# Tyr.net
KiCad netlist of a schematic drawn in EAGLE
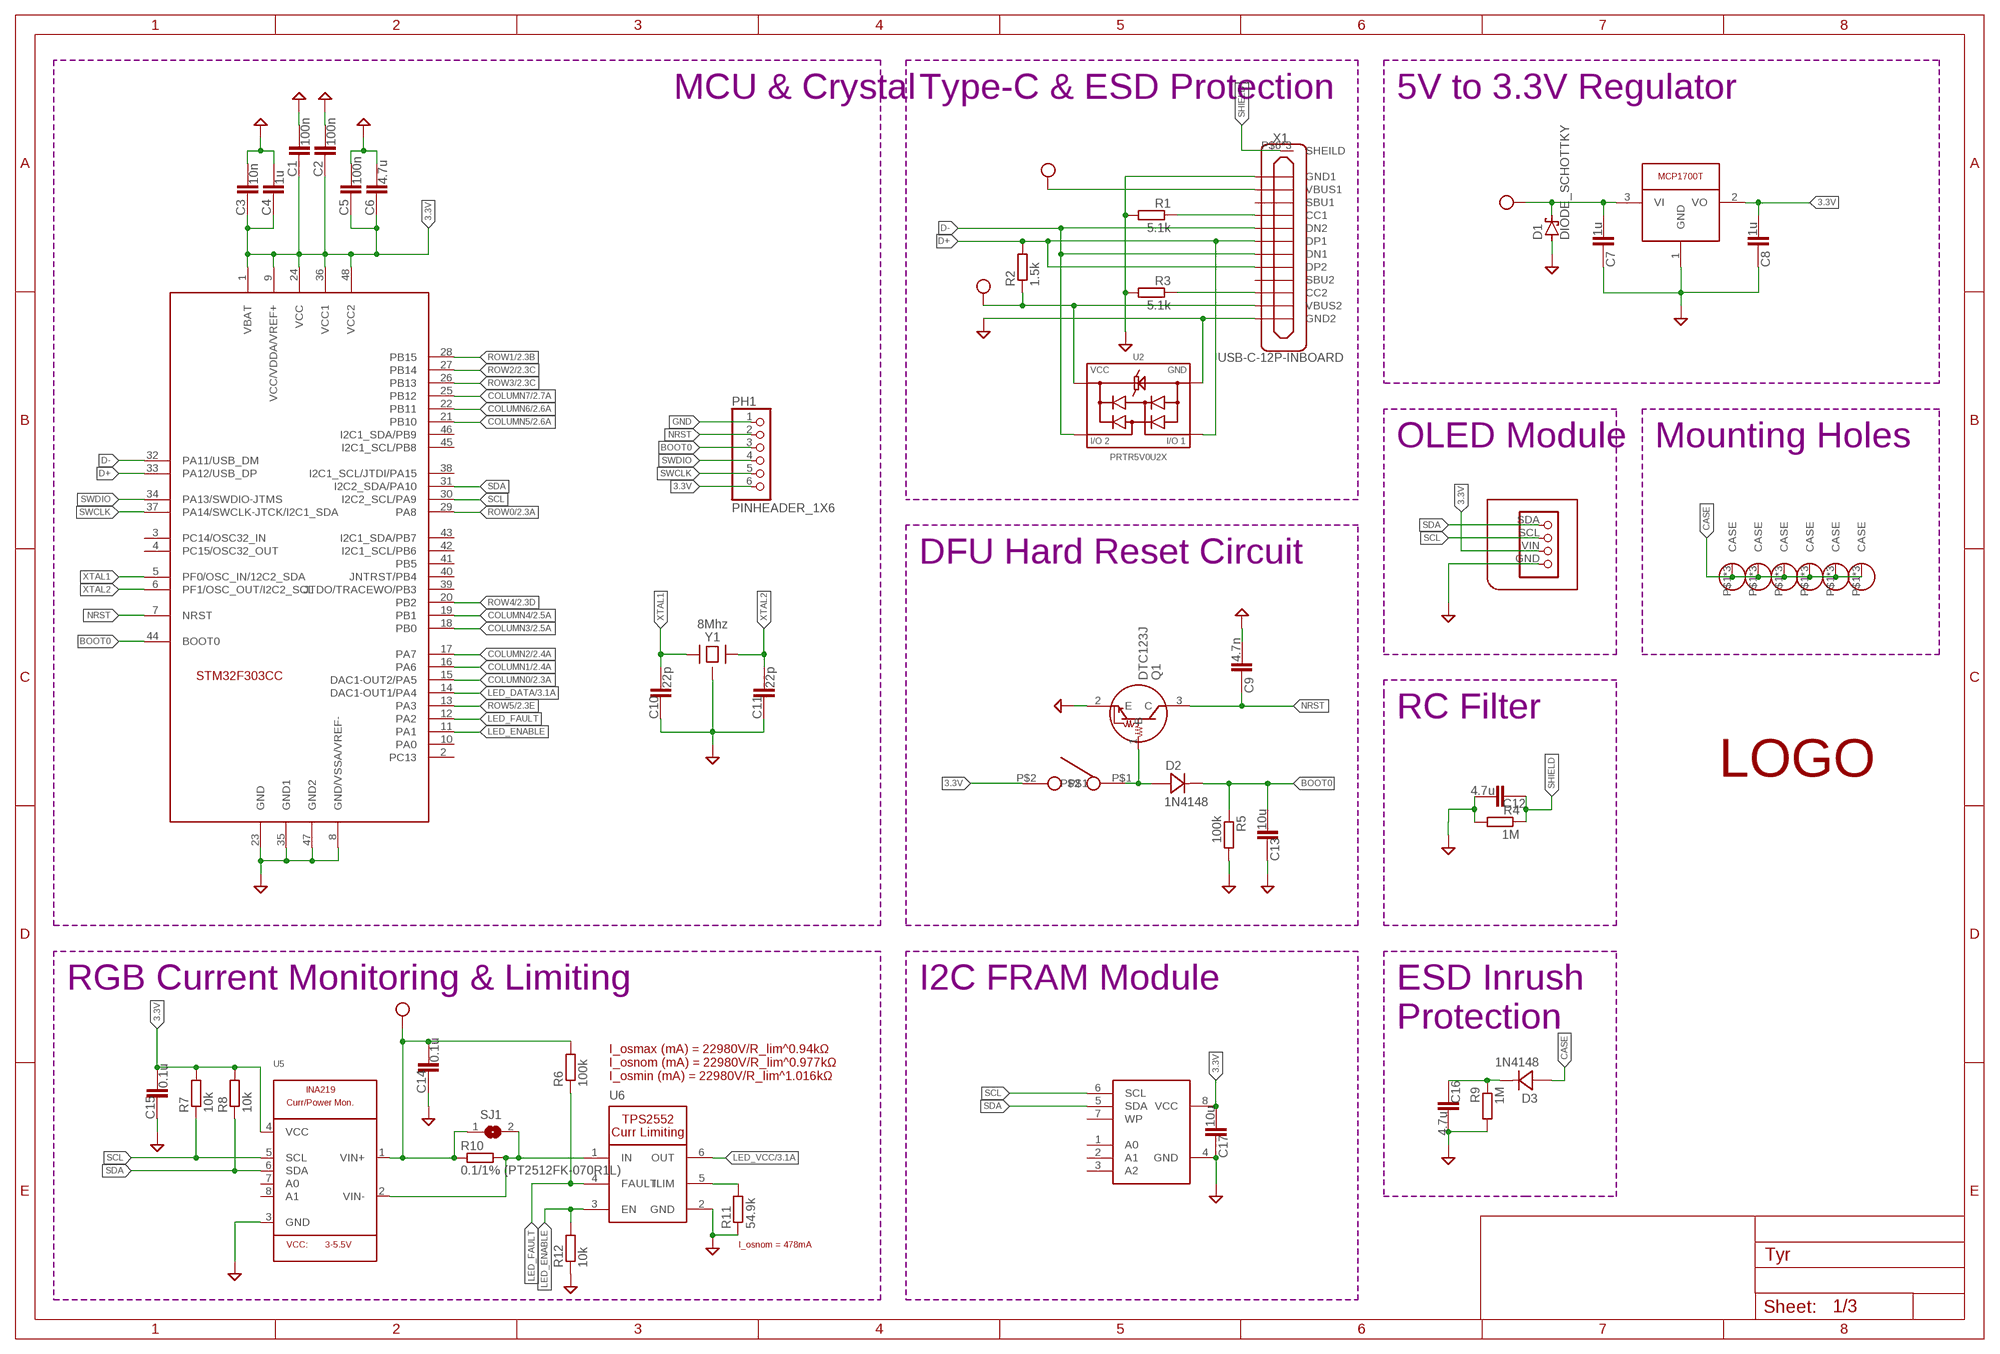
[diagram p0: schematic, sheet 1]
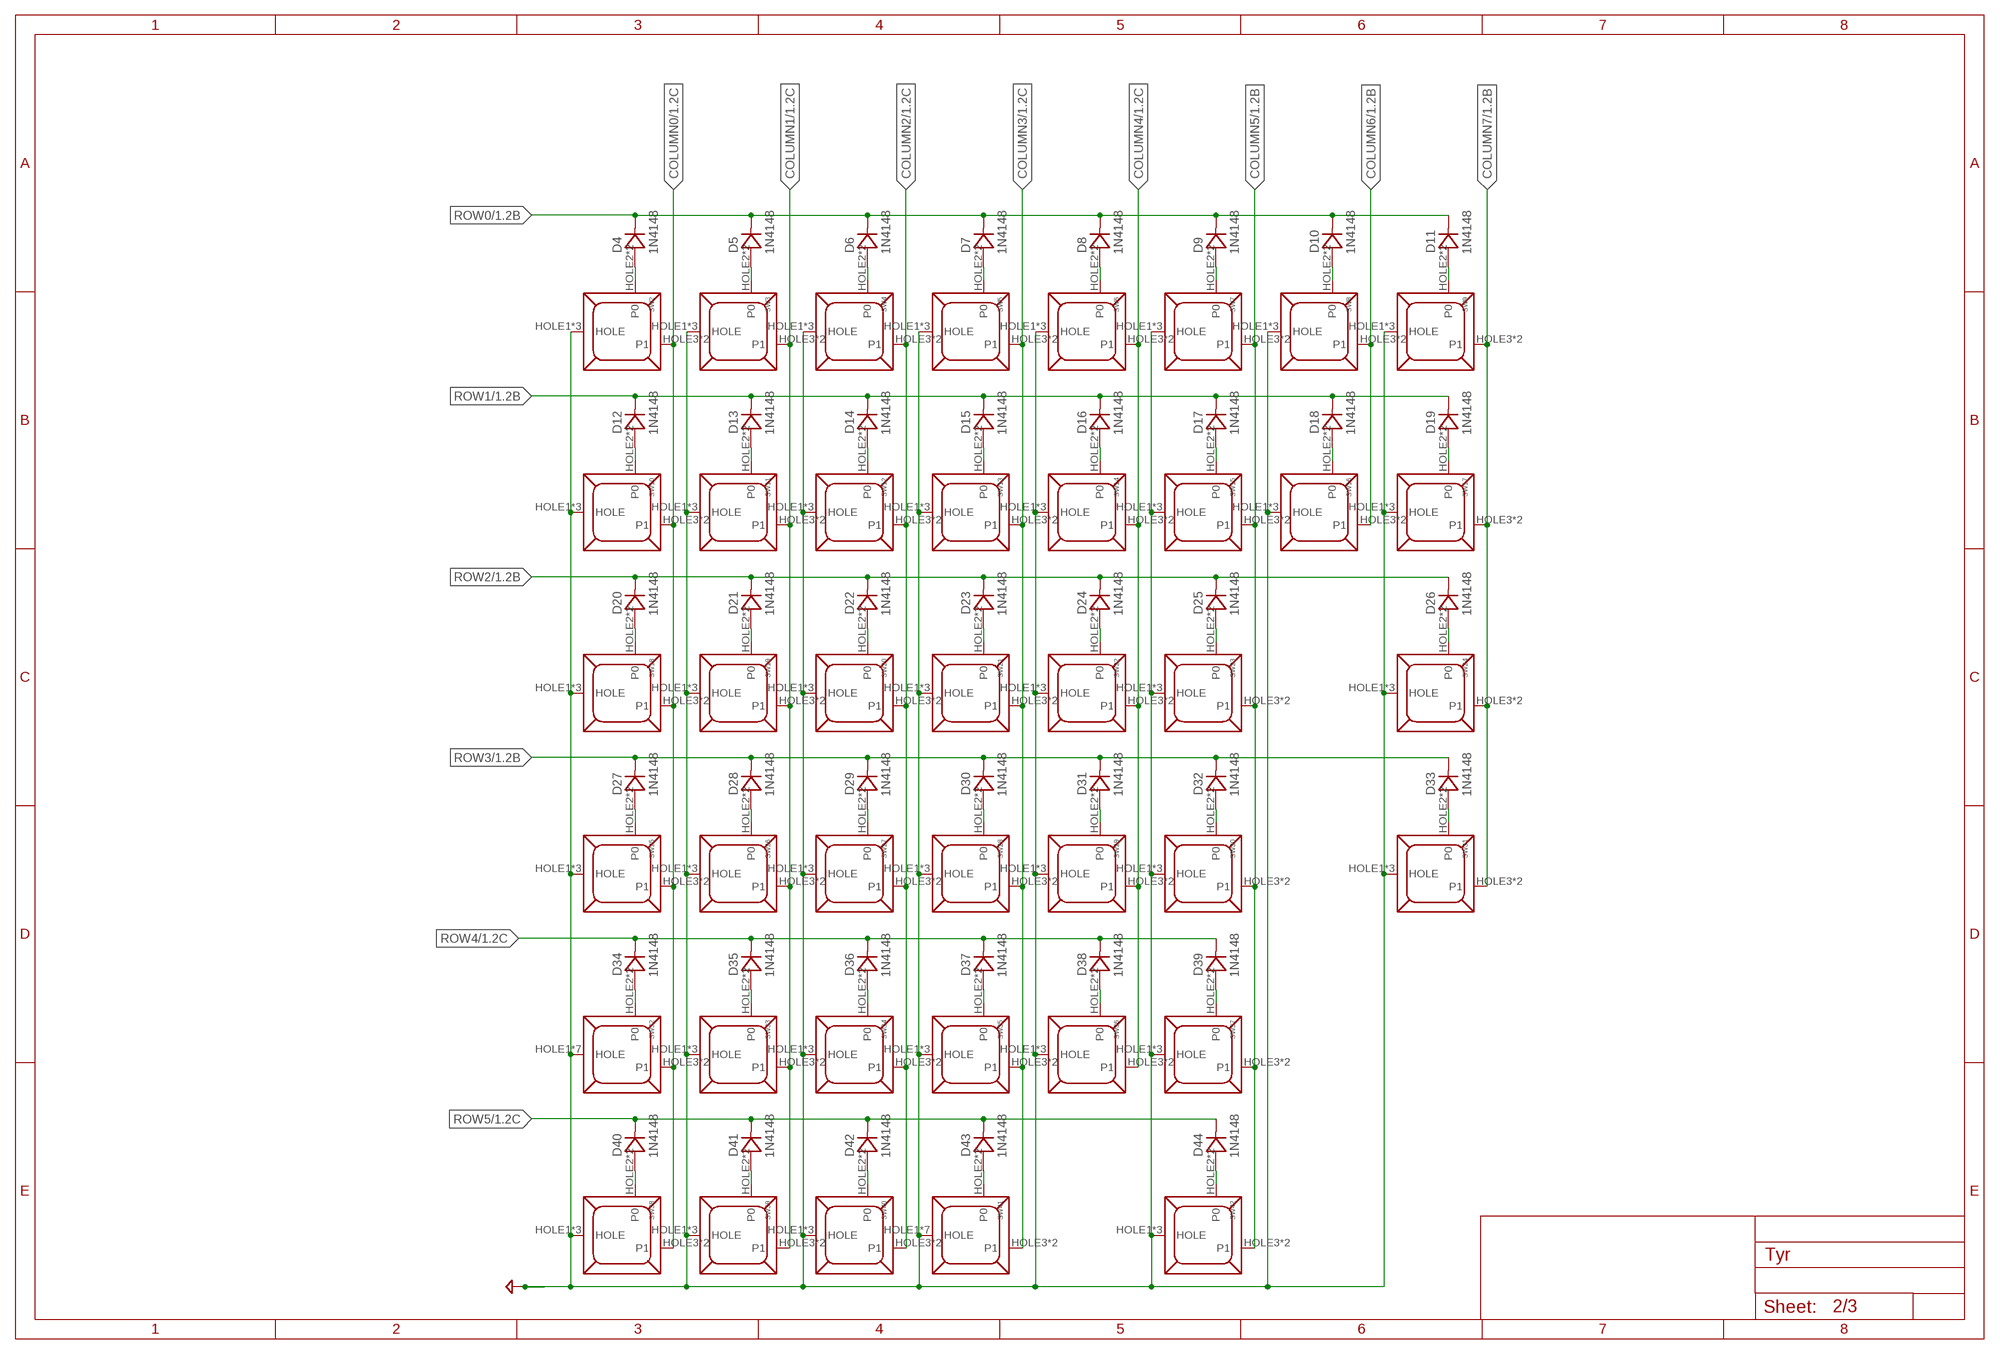
[diagram p1: schematic, sheet 2]
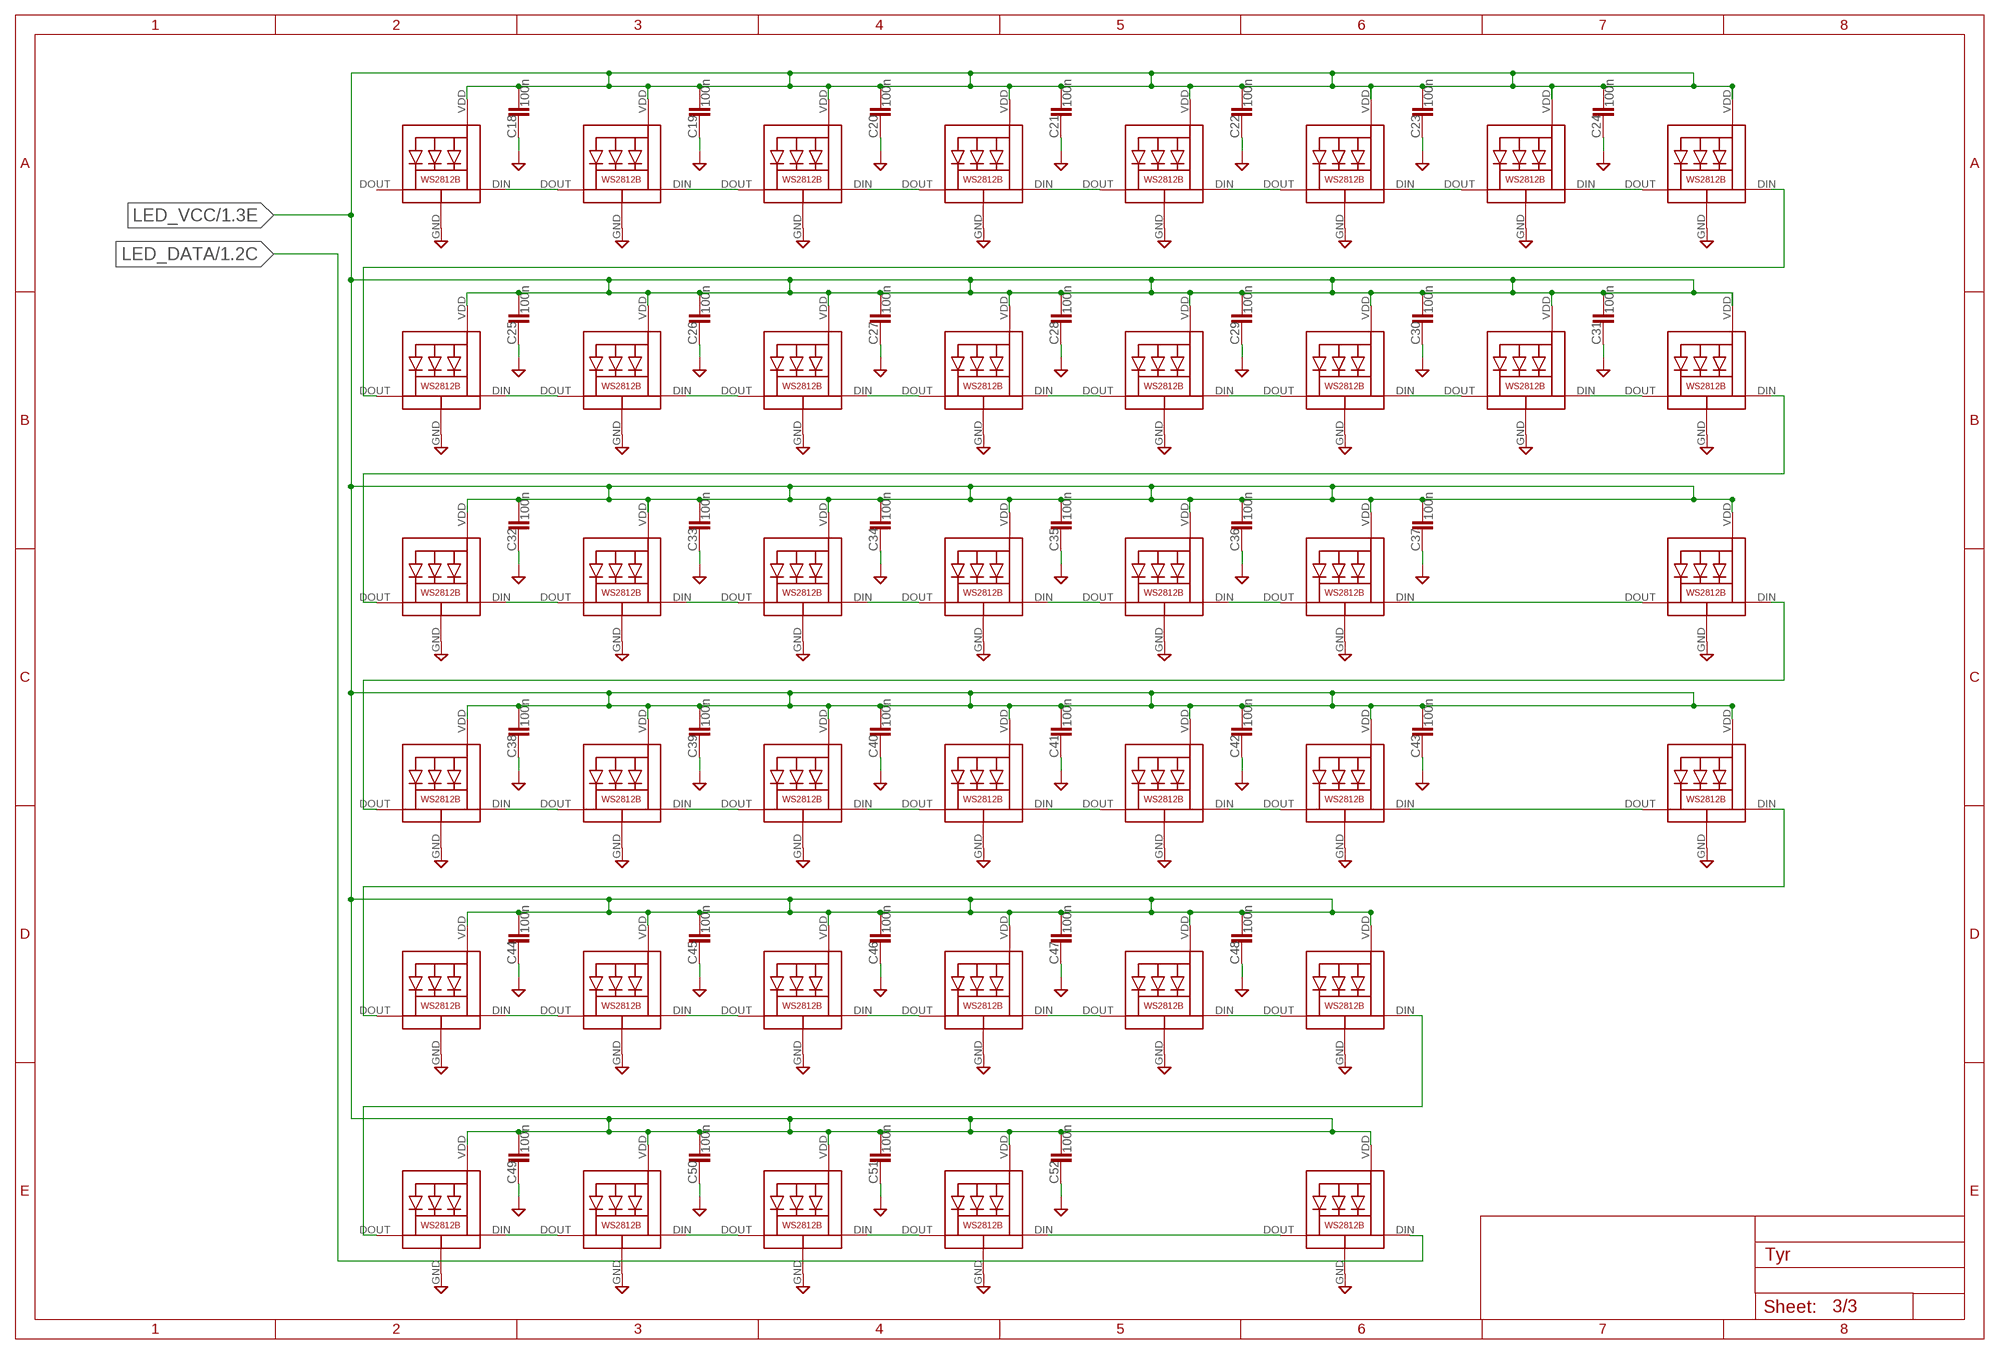
[diagram p2: schematic, sheet 3]

(export (version "E")
  (design (tool "Eeschema 10.0.6"))
  (components
    (comp (ref "D4")
      (value "1N4148")
      (footprint "eagle-import:SOD-123")
      (libsource (lib "eagle-import") (part "DIODE-SOD-123"))
    )
    (comp (ref "D5")
      (value "1N4148")
      (footprint "eagle-import:SOD-123")
      (libsource (lib "eagle-import") (part "DIODE-SOD-123"))
    )
    (comp (ref "D6")
      (value "1N4148")
      (footprint "eagle-import:SOD-123")
      (libsource (lib "eagle-import") (part "DIODE-SOD-123"))
    )
    (comp (ref "D7")
      (value "1N4148")
      (footprint "eagle-import:SOD-123")
      (libsource (lib "eagle-import") (part "DIODE-SOD-123"))
    )
    (comp (ref "D8")
      (value "1N4148")
      (footprint "eagle-import:SOD-123")
      (libsource (lib "eagle-import") (part "DIODE-SOD-123"))
    )
    (comp (ref "D9")
      (value "1N4148")
      (footprint "eagle-import:SOD-123")
      (libsource (lib "eagle-import") (part "DIODE-SOD-123"))
    )
    (comp (ref "D10")
      (value "1N4148")
      (footprint "eagle-import:SOD-123")
      (libsource (lib "eagle-import") (part "DIODE-SOD-123"))
    )
    (comp (ref "D11")
      (value "1N4148")
      (footprint "eagle-import:SOD-123")
      (libsource (lib "eagle-import") (part "DIODE-SOD-123"))
    )
    (comp (ref "D12")
      (value "1N4148")
      (footprint "eagle-import:SOD-123")
      (libsource (lib "eagle-import") (part "DIODE-SOD-123"))
    )
    (comp (ref "D13")
      (value "1N4148")
      (footprint "eagle-import:SOD-123")
      (libsource (lib "eagle-import") (part "DIODE-SOD-123"))
    )
    (comp (ref "D14")
      (value "1N4148")
      (footprint "eagle-import:SOD-123")
      (libsource (lib "eagle-import") (part "DIODE-SOD-123"))
    )
    (comp (ref "D15")
      (value "1N4148")
      (footprint "eagle-import:SOD-123")
      (libsource (lib "eagle-import") (part "DIODE-SOD-123"))
    )
    (comp (ref "D16")
      (value "1N4148")
      (footprint "eagle-import:SOD-123")
      (libsource (lib "eagle-import") (part "DIODE-SOD-123"))
    )
    (comp (ref "D17")
      (value "1N4148")
      (footprint "eagle-import:SOD-123")
      (libsource (lib "eagle-import") (part "DIODE-SOD-123"))
    )
    (comp (ref "D18")
      (value "1N4148")
      (footprint "eagle-import:SOD-123")
      (libsource (lib "eagle-import") (part "DIODE-SOD-123"))
    )
    (comp (ref "D19")
      (value "1N4148")
      (footprint "eagle-import:SOD-123")
      (libsource (lib "eagle-import") (part "DIODE-SOD-123"))
    )
    (comp (ref "D20")
      (value "1N4148")
      (footprint "eagle-import:SOD-123")
      (libsource (lib "eagle-import") (part "DIODE-SOD-123"))
    )
    (comp (ref "D21")
      (value "1N4148")
      (footprint "eagle-import:SOD-123")
      (libsource (lib "eagle-import") (part "DIODE-SOD-123"))
    )
    (comp (ref "D22")
      (value "1N4148")
      (footprint "eagle-import:SOD-123")
      (libsource (lib "eagle-import") (part "DIODE-SOD-123"))
    )
    (comp (ref "D23")
      (value "1N4148")
      (footprint "eagle-import:SOD-123")
      (libsource (lib "eagle-import") (part "DIODE-SOD-123"))
    )
    (comp (ref "D24")
      (value "1N4148")
      (footprint "eagle-import:SOD-123")
      (libsource (lib "eagle-import") (part "DIODE-SOD-123"))
    )
    (comp (ref "D25")
      (value "1N4148")
      (footprint "eagle-import:SOD-123")
      (libsource (lib "eagle-import") (part "DIODE-SOD-123"))
    )
    (comp (ref "D26")
      (value "1N4148")
      (footprint "eagle-import:SOD-123")
      (libsource (lib "eagle-import") (part "DIODE-SOD-123"))
    )
    (comp (ref "D27")
      (value "1N4148")
      (footprint "eagle-import:SOD-123")
      (libsource (lib "eagle-import") (part "DIODE-SOD-123"))
    )
    (comp (ref "D28")
      (value "1N4148")
      (footprint "eagle-import:SOD-123")
      (libsource (lib "eagle-import") (part "DIODE-SOD-123"))
    )
    (comp (ref "D29")
      (value "1N4148")
      (footprint "eagle-import:SOD-123")
      (libsource (lib "eagle-import") (part "DIODE-SOD-123"))
    )
    (comp (ref "D30")
      (value "1N4148")
      (footprint "eagle-import:SOD-123")
      (libsource (lib "eagle-import") (part "DIODE-SOD-123"))
    )
    (comp (ref "D31")
      (value "1N4148")
      (footprint "eagle-import:SOD-123")
      (libsource (lib "eagle-import") (part "DIODE-SOD-123"))
    )
    (comp (ref "D32")
      (value "1N4148")
      (footprint "eagle-import:SOD-123")
      (libsource (lib "eagle-import") (part "DIODE-SOD-123"))
    )
    (comp (ref "D33")
      (value "1N4148")
      (footprint "eagle-import:SOD-123")
      (libsource (lib "eagle-import") (part "DIODE-SOD-123"))
    )
    (comp (ref "D34")
      (value "1N4148")
      (footprint "eagle-import:SOD-123")
      (libsource (lib "eagle-import") (part "DIODE-SOD-123"))
    )
    (comp (ref "D35")
      (value "1N4148")
      (footprint "eagle-import:SOD-123")
      (libsource (lib "eagle-import") (part "DIODE-SOD-123"))
    )
    (comp (ref "D36")
      (value "1N4148")
      (footprint "eagle-import:SOD-123")
      (libsource (lib "eagle-import") (part "DIODE-SOD-123"))
    )
    (comp (ref "D37")
      (value "1N4148")
      (footprint "eagle-import:SOD-123")
      (libsource (lib "eagle-import") (part "DIODE-SOD-123"))
    )
    (comp (ref "D38")
      (value "1N4148")
      (footprint "eagle-import:SOD-123")
      (libsource (lib "eagle-import") (part "DIODE-SOD-123"))
    )
    (comp (ref "D39")
      (value "1N4148")
      (footprint "eagle-import:SOD-123")
      (libsource (lib "eagle-import") (part "DIODE-SOD-123"))
    )
    (comp (ref "D40")
      (value "1N4148")
      (footprint "eagle-import:SOD-123")
      (libsource (lib "eagle-import") (part "DIODE-SOD-123"))
    )
    (comp (ref "D41")
      (value "1N4148")
      (footprint "eagle-import:SOD-123")
      (libsource (lib "eagle-import") (part "DIODE-SOD-123"))
    )
    (comp (ref "D42")
      (value "1N4148")
      (footprint "eagle-import:SOD-123")
      (libsource (lib "eagle-import") (part "DIODE-SOD-123"))
    )
    (comp (ref "D43")
      (value "1N4148")
      (footprint "eagle-import:SOD-123")
      (libsource (lib "eagle-import") (part "DIODE-SOD-123"))
    )
    (comp (ref "D44")
      (value "1N4148")
      (footprint "eagle-import:SOD-123")
      (libsource (lib "eagle-import") (part "DIODE-SOD-123"))
    )
    (comp (ref "SW2")
      (value "MX")
      (footprint "eagle-import:MX-1U-HOTSWAP")
      (libsource (lib "eagle-import") (part "KEYSWITCH-MX_PLATED-1U-HOTSWAP"))
    )
    (comp (ref "SW3")
      (value "MX")
      (footprint "eagle-import:MX-1U-HOTSWAP")
      (libsource (lib "eagle-import") (part "KEYSWITCH-MX_PLATED-1U-HOTSWAP"))
    )
    (comp (ref "SW4")
      (value "MX")
      (footprint "eagle-import:MX-1U-HOTSWAP")
      (libsource (lib "eagle-import") (part "KEYSWITCH-MX_PLATED-1U-HOTSWAP"))
    )
    (comp (ref "SW5")
      (value "MX")
      (footprint "eagle-import:MX-1U-HOTSWAP")
      (libsource (lib "eagle-import") (part "KEYSWITCH-MX_PLATED-1U-HOTSWAP"))
    )
    (comp (ref "SW6")
      (value "MX")
      (footprint "eagle-import:MX-1U-HOTSWAP")
      (libsource (lib "eagle-import") (part "KEYSWITCH-MX_PLATED-1U-HOTSWAP"))
    )
    (comp (ref "SW7")
      (value "MX")
      (footprint "eagle-import:MX-1U-HOTSWAP")
      (libsource (lib "eagle-import") (part "KEYSWITCH-MX_PLATED-1U-HOTSWAP"))
    )
    (comp (ref "SW8")
      (value "MX")
      (footprint "eagle-import:MX-1U-HOTSWAP")
      (libsource (lib "eagle-import") (part "KEYSWITCH-MX_PLATED-1U-HOTSWAP"))
    )
    (comp (ref "SW9")
      (value "MX")
      (footprint "eagle-import:MX-1U-HOTSWAP")
      (libsource (lib "eagle-import") (part "KEYSWITCH-MX_PLATED-1U-HOTSWAP"))
    )
    (comp (ref "SW10")
      (value "MX")
      (footprint "eagle-import:MX-1U-HOTSWAP")
      (libsource (lib "eagle-import") (part "KEYSWITCH-MX_PLATED-1U-HOTSWAP"))
    )
    (comp (ref "SW11")
      (value "MX")
      (footprint "eagle-import:MX-1U-HOTSWAP")
      (libsource (lib "eagle-import") (part "KEYSWITCH-MX_PLATED-1U-HOTSWAP"))
    )
    (comp (ref "SW12")
      (value "MX")
      (footprint "eagle-import:MX-1U-HOTSWAP")
      (libsource (lib "eagle-import") (part "KEYSWITCH-MX_PLATED-1U-HOTSWAP"))
    )
    (comp (ref "SW13")
      (value "MX")
      (footprint "eagle-import:MX-1U-HOTSWAP")
      (libsource (lib "eagle-import") (part "KEYSWITCH-MX_PLATED-1U-HOTSWAP"))
    )
    (comp (ref "SW14")
      (value "MX")
      (footprint "eagle-import:MX-1U-HOTSWAP")
      (libsource (lib "eagle-import") (part "KEYSWITCH-MX_PLATED-1U-HOTSWAP"))
    )
    (comp (ref "SW15")
      (value "MX")
      (footprint "eagle-import:MX-1U-HOTSWAP")
      (libsource (lib "eagle-import") (part "KEYSWITCH-MX_PLATED-1U-HOTSWAP"))
    )
    (comp (ref "SW16")
      (value "MX")
      (footprint "eagle-import:MX-1U-HOTSWAP")
      (libsource (lib "eagle-import") (part "KEYSWITCH-MX_PLATED-1U-HOTSWAP"))
    )
    (comp (ref "SW17")
      (value "MX")
      (footprint "eagle-import:MX-1U-HOTSWAP")
      (libsource (lib "eagle-import") (part "KEYSWITCH-MX_PLATED-1U-HOTSWAP"))
    )
    (comp (ref "SW18")
      (value "MX")
      (footprint "eagle-import:MX-1U-HOTSWAP")
      (libsource (lib "eagle-import") (part "KEYSWITCH-MX_PLATED-1U-HOTSWAP"))
    )
    (comp (ref "SW19")
      (value "MX")
      (footprint "eagle-import:MX-1U-HOTSWAP")
      (libsource (lib "eagle-import") (part "KEYSWITCH-MX_PLATED-1U-HOTSWAP"))
    )
    (comp (ref "SW20")
      (value "MX")
      (footprint "eagle-import:MX-1U-HOTSWAP")
      (libsource (lib "eagle-import") (part "KEYSWITCH-MX_PLATED-1U-HOTSWAP"))
    )
    (comp (ref "SW21")
      (value "MX")
      (footprint "eagle-import:MX-1U-HOTSWAP")
      (libsource (lib "eagle-import") (part "KEYSWITCH-MX_PLATED-1U-HOTSWAP"))
    )
    (comp (ref "SW22")
      (value "MX")
      (footprint "eagle-import:MX-1U-HOTSWAP")
      (libsource (lib "eagle-import") (part "KEYSWITCH-MX_PLATED-1U-HOTSWAP"))
    )
    (comp (ref "SW23")
      (value "MX")
      (footprint "eagle-import:MX-1U-HOTSWAP")
      (libsource (lib "eagle-import") (part "KEYSWITCH-MX_PLATED-1U-HOTSWAP"))
    )
    (comp (ref "SW24")
      (value "MX")
      (footprint "eagle-import:MX-1U-HOTSWAP")
      (libsource (lib "eagle-import") (part "KEYSWITCH-MX_PLATED-1U-HOTSWAP"))
    )
    (comp (ref "SW25")
      (value "MX")
      (footprint "eagle-import:MX-1U-HOTSWAP-CAPSLOCK")
      (libsource (lib "eagle-import") (part "KEYSWITCH-MX_PLATED-1U-HOTSWAP_CAPSLOCK"))
    )
    (comp (ref "SW26")
      (value "MX")
      (footprint "eagle-import:MX-1U-HOTSWAP")
      (libsource (lib "eagle-import") (part "KEYSWITCH-MX_PLATED-1U-HOTSWAP"))
    )
    (comp (ref "SW27")
      (value "MX")
      (footprint "eagle-import:MX-1U-HOTSWAP")
      (libsource (lib "eagle-import") (part "KEYSWITCH-MX_PLATED-1U-HOTSWAP"))
    )
    (comp (ref "SW28")
      (value "MX")
      (footprint "eagle-import:MX-1U-HOTSWAP")
      (libsource (lib "eagle-import") (part "KEYSWITCH-MX_PLATED-1U-HOTSWAP"))
    )
    (comp (ref "SW29")
      (value "MX")
      (footprint "eagle-import:MX-1U-HOTSWAP")
      (libsource (lib "eagle-import") (part "KEYSWITCH-MX_PLATED-1U-HOTSWAP"))
    )
    (comp (ref "SW30")
      (value "MX")
      (footprint "eagle-import:MX-1U-HOTSWAP")
      (libsource (lib "eagle-import") (part "KEYSWITCH-MX_PLATED-1U-HOTSWAP"))
    )
    (comp (ref "SW31")
      (value "MX")
      (footprint "eagle-import:MX-1U-HOTSWAP")
      (libsource (lib "eagle-import") (part "KEYSWITCH-MX_PLATED-1U-HOTSWAP"))
    )
    (comp (ref "SW32")
      (value "MX")
      (footprint "eagle-import:MX-2U-HOTSWAP")
      (libsource (lib "eagle-import") (part "KEYSWITCH-MX_PLATED-2U-HOTSWAP"))
    )
    (comp (ref "SW33")
      (value "MX")
      (footprint "eagle-import:MX-1U-HOTSWAP")
      (libsource (lib "eagle-import") (part "KEYSWITCH-MX_PLATED-1U-HOTSWAP"))
    )
    (comp (ref "SW34")
      (value "MX")
      (footprint "eagle-import:MX-1U-HOTSWAP")
      (libsource (lib "eagle-import") (part "KEYSWITCH-MX_PLATED-1U-HOTSWAP"))
    )
    (comp (ref "SW35")
      (value "MX")
      (footprint "eagle-import:MX-1U-HOTSWAP")
      (libsource (lib "eagle-import") (part "KEYSWITCH-MX_PLATED-1U-HOTSWAP"))
    )
    (comp (ref "SW36")
      (value "MX")
      (footprint "eagle-import:MX-1U-HOTSWAP")
      (libsource (lib "eagle-import") (part "KEYSWITCH-MX_PLATED-1U-HOTSWAP"))
    )
    (comp (ref "SW37")
      (value "MX")
      (footprint "eagle-import:MX-1U-HOTSWAP")
      (libsource (lib "eagle-import") (part "KEYSWITCH-MX_PLATED-1U-HOTSWAP"))
    )
    (comp (ref "SW38")
      (value "MX")
      (footprint "eagle-import:MX-1U-HOTSWAP")
      (libsource (lib "eagle-import") (part "KEYSWITCH-MX_PLATED-1U-HOTSWAP"))
    )
    (comp (ref "SW39")
      (value "MX")
      (footprint "eagle-import:MX-1U-HOTSWAP")
      (libsource (lib "eagle-import") (part "KEYSWITCH-MX_PLATED-1U-HOTSWAP"))
    )
    (comp (ref "SW40")
      (value "MX")
      (footprint "eagle-import:MX-1U-HOTSWAP")
      (libsource (lib "eagle-import") (part "KEYSWITCH-MX_PLATED-1U-HOTSWAP"))
    )
    (comp (ref "SW41")
      (value "MX")
      (footprint "eagle-import:MX-2U-HOTSWAP")
      (libsource (lib "eagle-import") (part "KEYSWITCH-MX_PLATED-2U-HOTSWAP"))
    )
    (comp (ref "SW42")
      (value "MX")
      (footprint "eagle-import:MX-1U-HOTSWAP")
      (libsource (lib "eagle-import") (part "KEYSWITCH-MX_PLATED-1U-HOTSWAP"))
    )
    (comp (ref "C18")
      (value "100n")
      (footprint "eagle-import:C0603")
      (libsource (lib "eagle-import") (part "CAPACITOR-0603"))
    )
    (comp (ref "C19")
      (value "100n")
      (footprint "eagle-import:C0603")
      (libsource (lib "eagle-import") (part "CAPACITOR-0603"))
    )
    (comp (ref "C20")
      (value "100n")
      (footprint "eagle-import:C0603")
      (libsource (lib "eagle-import") (part "CAPACITOR-0603"))
    )
    (comp (ref "C21")
      (value "100n")
      (footprint "eagle-import:C0603")
      (libsource (lib "eagle-import") (part "CAPACITOR-0603"))
    )
    (comp (ref "C22")
      (value "100n")
      (footprint "eagle-import:C0603")
      (libsource (lib "eagle-import") (part "CAPACITOR-0603"))
    )
    (comp (ref "C23")
      (value "100n")
      (footprint "eagle-import:C0603")
      (libsource (lib "eagle-import") (part "CAPACITOR-0603"))
    )
    (comp (ref "C24")
      (value "100n")
      (footprint "eagle-import:C0603")
      (libsource (lib "eagle-import") (part "CAPACITOR-0603"))
    )
    (comp (ref "C25")
      (value "100n")
      (footprint "eagle-import:C0603")
      (libsource (lib "eagle-import") (part "CAPACITOR-0603"))
    )
    (comp (ref "C26")
      (value "100n")
      (footprint "eagle-import:C0603")
      (libsource (lib "eagle-import") (part "CAPACITOR-0603"))
    )
    (comp (ref "C27")
      (value "100n")
      (footprint "eagle-import:C0603")
      (libsource (lib "eagle-import") (part "CAPACITOR-0603"))
    )
    (comp (ref "C28")
      (value "100n")
      (footprint "eagle-import:C0603")
      (libsource (lib "eagle-import") (part "CAPACITOR-0603"))
    )
    (comp (ref "C29")
      (value "100n")
      (footprint "eagle-import:C0603")
      (libsource (lib "eagle-import") (part "CAPACITOR-0603"))
    )
    (comp (ref "C30")
      (value "100n")
      (footprint "eagle-import:C0603")
      (libsource (lib "eagle-import") (part "CAPACITOR-0603"))
    )
    (comp (ref "C31")
      (value "100n")
      (footprint "eagle-import:C0603")
      (libsource (lib "eagle-import") (part "CAPACITOR-0603"))
    )
    (comp (ref "C32")
      (value "100n")
      (footprint "eagle-import:C0603")
      (libsource (lib "eagle-import") (part "CAPACITOR-0603"))
    )
    (comp (ref "C33")
      (value "100n")
      (footprint "eagle-import:C0603")
      (libsource (lib "eagle-import") (part "CAPACITOR-0603"))
    )
    (comp (ref "C34")
      (value "100n")
      (footprint "eagle-import:C0603")
      (libsource (lib "eagle-import") (part "CAPACITOR-0603"))
    )
    (comp (ref "C35")
      (value "100n")
      (footprint "eagle-import:C0603")
      (libsource (lib "eagle-import") (part "CAPACITOR-0603"))
    )
    (comp (ref "C36")
      (value "100n")
      (footprint "eagle-import:C0603")
      (libsource (lib "eagle-import") (part "CAPACITOR-0603"))
    )
    (comp (ref "C37")
      (value "100n")
      (footprint "eagle-import:C0603")
      (libsource (lib "eagle-import") (part "CAPACITOR-0603"))
    )
    (comp (ref "C38")
      (value "100n")
      (footprint "eagle-import:C0603")
      (libsource (lib "eagle-import") (part "CAPACITOR-0603"))
    )
    (comp (ref "C39")
      (value "100n")
      (footprint "eagle-import:C0603")
      (libsource (lib "eagle-import") (part "CAPACITOR-0603"))
    )
    (comp (ref "C40")
      (value "100n")
      (footprint "eagle-import:C0603")
      (libsource (lib "eagle-import") (part "CAPACITOR-0603"))
    )
    (comp (ref "C41")
      (value "100n")
      (footprint "eagle-import:C0603")
      (libsource (lib "eagle-import") (part "CAPACITOR-0603"))
    )
    (comp (ref "C42")
      (value "100n")
      (footprint "eagle-import:C0603")
      (libsource (lib "eagle-import") (part "CAPACITOR-0603"))
    )
    (comp (ref "C43")
      (value "100n")
      (footprint "eagle-import:C0603")
      (libsource (lib "eagle-import") (part "CAPACITOR-0603"))
    )
    (comp (ref "C44")
      (value "100n")
      (footprint "eagle-import:C0603")
      (libsource (lib "eagle-import") (part "CAPACITOR-0603"))
    )
    (comp (ref "C45")
      (value "100n")
      (footprint "eagle-import:C0603")
      (libsource (lib "eagle-import") (part "CAPACITOR-0603"))
    )
    (comp (ref "C46")
      (value "100n")
      (footprint "eagle-import:C0603")
      (libsource (lib "eagle-import") (part "CAPACITOR-0603"))
    )
    (comp (ref "C47")
      (value "100n")
      (footprint "eagle-import:C0603")
      (libsource (lib "eagle-import") (part "CAPACITOR-0603"))
    )
    (comp (ref "C48")
      (value "100n")
      (footprint "eagle-import:C0603")
      (libsource (lib "eagle-import") (part "CAPACITOR-0603"))
    )
    (comp (ref "C49")
      (value "100n")
      (footprint "eagle-import:C0603")
      (libsource (lib "eagle-import") (part "CAPACITOR-0603"))
    )
    (comp (ref "C50")
      (value "100n")
      (footprint "eagle-import:C0603")
      (libsource (lib "eagle-import") (part "CAPACITOR-0603"))
    )
    (comp (ref "C51")
      (value "100n")
      (footprint "eagle-import:C0603")
      (libsource (lib "eagle-import") (part "CAPACITOR-0603"))
    )
    (comp (ref "C52")
      (value "100n")
      (footprint "eagle-import:C0603")
      (libsource (lib "eagle-import") (part "CAPACITOR-0603"))
    )
    (comp (ref "LED1")
      (value "WS2812B_3528_REVERS-MOUNT")
      (footprint "eagle-import:WS2812B_3528_REVERS-MOUNT")
      (libsource (lib "eagle-import") (part "WS2812B_3528_REVERS-MOUNT"))
    )
    (comp (ref "LED2")
      (value "WS2812B_3528_REVERS-MOUNT")
      (footprint "eagle-import:WS2812B_3528_REVERS-MOUNT")
      (libsource (lib "eagle-import") (part "WS2812B_3528_REVERS-MOUNT"))
    )
    (comp (ref "LED3")
      (value "WS2812B_3528_REVERS-MOUNT")
      (footprint "eagle-import:WS2812B_3528_REVERS-MOUNT")
      (libsource (lib "eagle-import") (part "WS2812B_3528_REVERS-MOUNT"))
    )
    (comp (ref "LED4")
      (value "WS2812B_3528_REVERS-MOUNT")
      (footprint "eagle-import:WS2812B_3528_REVERS-MOUNT")
      (libsource (lib "eagle-import") (part "WS2812B_3528_REVERS-MOUNT"))
    )
    (comp (ref "LED5")
      (value "WS2812B_3528_REVERS-MOUNT")
      (footprint "eagle-import:WS2812B_3528_REVERS-MOUNT")
      (libsource (lib "eagle-import") (part "WS2812B_3528_REVERS-MOUNT"))
    )
    (comp (ref "LED6")
      (value "WS2812B_3528_REVERS-MOUNT")
      (footprint "eagle-import:WS2812B_3528_REVERS-MOUNT")
      (libsource (lib "eagle-import") (part "WS2812B_3528_REVERS-MOUNT"))
    )
    (comp (ref "LED7")
      (value "WS2812B_3528_REVERS-MOUNT")
      (footprint "eagle-import:WS2812B_3528_REVERS-MOUNT")
      (libsource (lib "eagle-import") (part "WS2812B_3528_REVERS-MOUNT"))
    )
    (comp (ref "LED8")
      (value "WS2812B_3528_REVERS-MOUNT")
      (footprint "eagle-import:WS2812B_3528_REVERS-MOUNT")
      (libsource (lib "eagle-import") (part "WS2812B_3528_REVERS-MOUNT"))
    )
    (comp (ref "LED9")
      (value "WS2812B_3528_REVERS-MOUNT")
      (footprint "eagle-import:WS2812B_3528_REVERS-MOUNT")
      (libsource (lib "eagle-import") (part "WS2812B_3528_REVERS-MOUNT"))
    )
    (comp (ref "LED10")
      (value "WS2812B_3528_REVERS-MOUNT")
      (footprint "eagle-import:WS2812B_3528_REVERS-MOUNT")
      (libsource (lib "eagle-import") (part "WS2812B_3528_REVERS-MOUNT"))
    )
    (comp (ref "LED11")
      (value "WS2812B_3528_REVERS-MOUNT")
      (footprint "eagle-import:WS2812B_3528_REVERS-MOUNT")
      (libsource (lib "eagle-import") (part "WS2812B_3528_REVERS-MOUNT"))
    )
    (comp (ref "LED12")
      (value "WS2812B_3528_REVERS-MOUNT")
      (footprint "eagle-import:WS2812B_3528_REVERS-MOUNT")
      (libsource (lib "eagle-import") (part "WS2812B_3528_REVERS-MOUNT"))
    )
    (comp (ref "LED13")
      (value "WS2812B_3528_REVERS-MOUNT")
      (footprint "eagle-import:WS2812B_3528_REVERS-MOUNT")
      (libsource (lib "eagle-import") (part "WS2812B_3528_REVERS-MOUNT"))
    )
    (comp (ref "LED14")
      (value "WS2812B_3528_REVERS-MOUNT")
      (footprint "eagle-import:WS2812B_3528_REVERS-MOUNT")
      (libsource (lib "eagle-import") (part "WS2812B_3528_REVERS-MOUNT"))
    )
    (comp (ref "LED15")
      (value "WS2812B_3528_REVERS-MOUNT")
      (footprint "eagle-import:WS2812B_3528_REVERS-MOUNT")
      (libsource (lib "eagle-import") (part "WS2812B_3528_REVERS-MOUNT"))
    )
    (comp (ref "LED16")
      (value "WS2812B_3528_REVERS-MOUNT")
      (footprint "eagle-import:WS2812B_3528_REVERS-MOUNT")
      (libsource (lib "eagle-import") (part "WS2812B_3528_REVERS-MOUNT"))
    )
    (comp (ref "LED17")
      (value "WS2812B_3528_REVERS-MOUNT")
      (footprint "eagle-import:WS2812B_3528_REVERS-MOUNT")
      (libsource (lib "eagle-import") (part "WS2812B_3528_REVERS-MOUNT"))
    )
    (comp (ref "LED18")
      (value "WS2812B_3528_REVERS-MOUNT")
      (footprint "eagle-import:WS2812B_3528_REVERS-MOUNT")
      (libsource (lib "eagle-import") (part "WS2812B_3528_REVERS-MOUNT"))
    )
    (comp (ref "LED19")
      (value "WS2812B_3528_REVERS-MOUNT")
      (footprint "eagle-import:WS2812B_3528_REVERS-MOUNT")
      (libsource (lib "eagle-import") (part "WS2812B_3528_REVERS-MOUNT"))
    )
    (comp (ref "LED20")
      (value "WS2812B_3528_REVERS-MOUNT")
      (footprint "eagle-import:WS2812B_3528_REVERS-MOUNT")
      (libsource (lib "eagle-import") (part "WS2812B_3528_REVERS-MOUNT"))
    )
    (comp (ref "LED21")
      (value "WS2812B_3528_REVERS-MOUNT")
      (footprint "eagle-import:WS2812B_3528_REVERS-MOUNT")
      (libsource (lib "eagle-import") (part "WS2812B_3528_REVERS-MOUNT"))
    )
    (comp (ref "LED22")
      (value "WS2812B_3528_REVERS-MOUNT")
      (footprint "eagle-import:WS2812B_3528_REVERS-MOUNT")
      (libsource (lib "eagle-import") (part "WS2812B_3528_REVERS-MOUNT"))
    )
    (comp (ref "LED23")
      (value "WS2812B_3528_REVERS-MOUNT")
      (footprint "eagle-import:WS2812B_3528_REVERS-MOUNT")
      (libsource (lib "eagle-import") (part "WS2812B_3528_REVERS-MOUNT"))
    )
    (comp (ref "LED24")
      (value "WS2812B_3528_REVERS-MOUNT")
      (footprint "eagle-import:WS2812B_3528_REVERS-MOUNT")
      (libsource (lib "eagle-import") (part "WS2812B_3528_REVERS-MOUNT"))
    )
    (comp (ref "LED25")
      (value "WS2812B_3528_REVERS-MOUNT")
      (footprint "eagle-import:WS2812B_3528_REVERS-MOUNT")
      (libsource (lib "eagle-import") (part "WS2812B_3528_REVERS-MOUNT"))
    )
    (comp (ref "LED26")
      (value "WS2812B_3528_REVERS-MOUNT")
      (footprint "eagle-import:WS2812B_3528_REVERS-MOUNT")
      (libsource (lib "eagle-import") (part "WS2812B_3528_REVERS-MOUNT"))
    )
    (comp (ref "LED27")
      (value "WS2812B_3528_REVERS-MOUNT")
      (footprint "eagle-import:WS2812B_3528_REVERS-MOUNT")
      (libsource (lib "eagle-import") (part "WS2812B_3528_REVERS-MOUNT"))
    )
    (comp (ref "LED28")
      (value "WS2812B_3528_REVERS-MOUNT")
      (footprint "eagle-import:WS2812B_3528_REVERS-MOUNT")
      (libsource (lib "eagle-import") (part "WS2812B_3528_REVERS-MOUNT"))
    )
    (comp (ref "LED29")
      (value "WS2812B_3528_REVERS-MOUNT")
      (footprint "eagle-import:WS2812B_3528_REVERS-MOUNT")
      (libsource (lib "eagle-import") (part "WS2812B_3528_REVERS-MOUNT"))
    )
    (comp (ref "LED30")
      (value "WS2812B_3528_REVERS-MOUNT")
      (footprint "eagle-import:WS2812B_3528_REVERS-MOUNT")
      (libsource (lib "eagle-import") (part "WS2812B_3528_REVERS-MOUNT"))
    )
    (comp (ref "LED31")
      (value "WS2812B_3528_REVERS-MOUNT")
      (footprint "eagle-import:WS2812B_3528_REVERS-MOUNT")
      (libsource (lib "eagle-import") (part "WS2812B_3528_REVERS-MOUNT"))
    )
    (comp (ref "LED32")
      (value "WS2812B_3528_REVERS-MOUNT")
      (footprint "eagle-import:WS2812B_3528_REVERS-MOUNT")
      (libsource (lib "eagle-import") (part "WS2812B_3528_REVERS-MOUNT"))
    )
    (comp (ref "LED33")
      (value "WS2812B_3528_REVERS-MOUNT")
      (footprint "eagle-import:WS2812B_3528_REVERS-MOUNT")
      (libsource (lib "eagle-import") (part "WS2812B_3528_REVERS-MOUNT"))
    )
    (comp (ref "LED34")
      (value "WS2812B_3528_REVERS-MOUNT")
      (footprint "eagle-import:WS2812B_3528_REVERS-MOUNT")
      (libsource (lib "eagle-import") (part "WS2812B_3528_REVERS-MOUNT"))
    )
    (comp (ref "LED35")
      (value "WS2812B_3528_REVERS-MOUNT")
      (footprint "eagle-import:WS2812B_3528_REVERS-MOUNT")
      (libsource (lib "eagle-import") (part "WS2812B_3528_REVERS-MOUNT"))
    )
    (comp (ref "LED36")
      (value "WS2812B_3528_REVERS-MOUNT")
      (footprint "eagle-import:WS2812B_3528_REVERS-MOUNT")
      (libsource (lib "eagle-import") (part "WS2812B_3528_REVERS-MOUNT"))
    )
    (comp (ref "LED37")
      (value "WS2812B_3528_REVERS-MOUNT")
      (footprint "eagle-import:WS2812B_3528_REVERS-MOUNT")
      (libsource (lib "eagle-import") (part "WS2812B_3528_REVERS-MOUNT"))
    )
    (comp (ref "LED38")
      (value "WS2812B_3528_REVERS-MOUNT")
      (footprint "eagle-import:WS2812B_3528_REVERS-MOUNT")
      (libsource (lib "eagle-import") (part "WS2812B_3528_REVERS-MOUNT"))
    )
    (comp (ref "LED39")
      (value "WS2812B_3528_REVERS-MOUNT")
      (footprint "eagle-import:WS2812B_3528_REVERS-MOUNT")
      (libsource (lib "eagle-import") (part "WS2812B_3528_REVERS-MOUNT"))
    )
    (comp (ref "LED40")
      (value "WS2812B_3528_REVERS-MOUNT")
      (footprint "eagle-import:WS2812B_3528_REVERS-MOUNT")
      (libsource (lib "eagle-import") (part "WS2812B_3528_REVERS-MOUNT"))
    )
    (comp (ref "LED41")
      (value "WS2812B_3528_REVERS-MOUNT")
      (footprint "eagle-import:WS2812B_3528_REVERS-MOUNT")
      (libsource (lib "eagle-import") (part "WS2812B_3528_REVERS-MOUNT"))
    )
    (comp (ref "C1")
      (value "100n")
      (footprint "eagle-import:C0603")
      (libsource (lib "eagle-import") (part "CAPACITOR-0603"))
    )
    (comp (ref "C2")
      (value "100n")
      (footprint "eagle-import:C0603")
      (libsource (lib "eagle-import") (part "CAPACITOR-0603"))
    )
    (comp (ref "C3")
      (value "10n")
      (footprint "eagle-import:C0603")
      (libsource (lib "eagle-import") (part "CAPACITOR-0603"))
    )
    (comp (ref "C4")
      (value "1u")
      (footprint "eagle-import:C0603")
      (libsource (lib "eagle-import") (part "CAPACITOR-0603"))
    )
    (comp (ref "C5")
      (value "100n")
      (footprint "eagle-import:C0603")
      (libsource (lib "eagle-import") (part "CAPACITOR-0603"))
    )
    (comp (ref "C6")
      (value "4.7u")
      (footprint "eagle-import:C0603")
      (libsource (lib "eagle-import") (part "CAPACITOR-0603"))
    )
    (comp (ref "C7")
      (value "1u")
      (footprint "eagle-import:C0603")
      (libsource (lib "eagle-import") (part "CAPACITOR-0603"))
    )
    (comp (ref "C8")
      (value "1u")
      (footprint "eagle-import:C0603")
      (libsource (lib "eagle-import") (part "CAPACITOR-0603"))
    )
    (comp (ref "C9")
      (value "4.7n")
      (footprint "eagle-import:C0603")
      (libsource (lib "eagle-import") (part "CAPACITOR-0603"))
    )
    (comp (ref "C10")
      (value "22p")
      (footprint "eagle-import:C0603")
      (libsource (lib "eagle-import") (part "CAPACITOR-0603"))
    )
    (comp (ref "C11")
      (value "22p")
      (footprint "eagle-import:C0603")
      (libsource (lib "eagle-import") (part "CAPACITOR-0603"))
    )
    (comp (ref "C12")
      (value "4.7u")
      (footprint "eagle-import:C0603")
      (libsource (lib "eagle-import") (part "CAPACITOR-0603"))
    )
    (comp (ref "C13")
      (value "10u")
      (footprint "eagle-import:C0603")
      (libsource (lib "eagle-import") (part "CAPACITOR-0603"))
    )
    (comp (ref "C14")
      (value "0.1u")
      (footprint "eagle-import:C0603")
      (libsource (lib "eagle-import") (part "CAPACITOR-0603"))
    )
    (comp (ref "C15")
      (value "0.1u")
      (footprint "eagle-import:C0603")
      (libsource (lib "eagle-import") (part "CAPACITOR-0603"))
    )
    (comp (ref "C16")
      (value "4.7u")
      (footprint "eagle-import:C0603")
      (libsource (lib "eagle-import") (part "CAPACITOR-0603"))
    )
    (comp (ref "C17")
      (value "10u")
      (footprint "eagle-import:C0603")
      (libsource (lib "eagle-import") (part "CAPACITOR-0603"))
    )
    (comp (ref "D1")
      (value "DIODE_SCHOTTKY")
      (footprint "eagle-import:SOD-123")
      (libsource (lib "eagle-import") (part "DIODE_SCHOTTKY"))
    )
    (comp (ref "D2")
      (value "1N4148")
      (footprint "eagle-import:SOD-123")
      (libsource (lib "eagle-import") (part "DIODE-SOD-123"))
    )
    (comp (ref "D3")
      (value "1N4148")
      (footprint "eagle-import:SOD-123")
      (libsource (lib "eagle-import") (part "DIODE-SOD-123"))
    )
    (comp (ref "HOLE1")
      (value "MOUNT_HOLE-5MM_NOTCH")
      (footprint "eagle-import:HOLE_5MM_OVAL")
      (libsource (lib "eagle-import") (part "MOUNT_HOLE-5MM_NOTCH"))
    )
    (comp (ref "HOLE2")
      (value "MOUNT_HOLE-5MM_NOTCH")
      (footprint "eagle-import:HOLE_5MM_OVAL")
      (libsource (lib "eagle-import") (part "MOUNT_HOLE-5MM_NOTCH"))
    )
    (comp (ref "HOLE3")
      (value "MOUNT_HOLE")
      (footprint "eagle-import:HOLE_M3_OVAL")
      (libsource (lib "eagle-import") (part "MOUNT_HOLE"))
    )
    (comp (ref "HOLE4")
      (value "MOUNT_HOLE")
      (footprint "eagle-import:HOLE_M3_OVAL")
      (libsource (lib "eagle-import") (part "MOUNT_HOLE"))
    )
    (comp (ref "HOLE5")
      (value "MOUNT_HOLE")
      (footprint "eagle-import:HOLE_M3_OVAL")
      (libsource (lib "eagle-import") (part "MOUNT_HOLE"))
    )
    (comp (ref "HOLE6")
      (value "MOUNT_HOLE")
      (footprint "eagle-import:HOLE_M3_OVAL")
      (libsource (lib "eagle-import") (part "MOUNT_HOLE"))
    )
    (comp (ref "J1")
      (value "TYR_DISPLAY")
      (footprint "eagle-import:TYR_TYR_DISPLAY")
      (libsource (lib "eagle-import") (part "TYR_DISPLAY"))
    )
    (comp (ref "LOGO1")
      (value "LOGO_TYR")
      (footprint "eagle-import:LOGO_TYR_COPPER")
      (libsource (lib "eagle-import") (part "LOGO_TYR"))
    )
    (comp (ref "PH1")
      (value "PINHEADER_1X6")
      (footprint "eagle-import:1X06")
      (libsource (lib "eagle-import") (part "PINHEADER_1X6"))
    )
    (comp (ref "Q1")
      (value "DTC123J")
      (footprint "eagle-import:SOT-323")
      (libsource (lib "eagle-import") (part "DTC123J"))
    )
    (comp (ref "R1")
      (value "5.1k")
      (footprint "eagle-import:R0603")
      (libsource (lib "eagle-import") (part "RESISTOR-0603"))
    )
    (comp (ref "R2")
      (value "1.5k")
      (footprint "eagle-import:R0603")
      (libsource (lib "eagle-import") (part "RESISTOR-0603"))
    )
    (comp (ref "R3")
      (value "5.1k")
      (footprint "eagle-import:R0603")
      (libsource (lib "eagle-import") (part "RESISTOR-0603"))
    )
    (comp (ref "R4")
      (value "1M")
      (footprint "eagle-import:R0603")
      (libsource (lib "eagle-import") (part "RESISTOR-0603"))
    )
    (comp (ref "R5")
      (value "100k")
      (footprint "eagle-import:R0603")
      (libsource (lib "eagle-import") (part "RESISTOR-0603"))
    )
    (comp (ref "R6")
      (value "100k")
      (footprint "eagle-import:R0603")
      (libsource (lib "eagle-import") (part "RESISTOR-0603"))
    )
    (comp (ref "R7")
      (value "10k")
      (footprint "eagle-import:R0603")
      (libsource (lib "eagle-import") (part "RESISTOR-0603"))
    )
    (comp (ref "R8")
      (value "10k")
      (footprint "eagle-import:R0603")
      (libsource (lib "eagle-import") (part "RESISTOR-0603"))
    )
    (comp (ref "R9")
      (value "1M")
      (footprint "eagle-import:R0603")
      (libsource (lib "eagle-import") (part "RESISTOR-0603"))
    )
    (comp (ref "R10")
      (value "0.1/1% (PT2512FK-070R1L)")
      (footprint "eagle-import:R2512")
      (libsource (lib "eagle-import") (part "RESISTOR-2512"))
    )
    (comp (ref "R11")
      (value "54.9k")
      (footprint "eagle-import:R0603")
      (libsource (lib "eagle-import") (part "RESISTOR-0603"))
    )
    (comp (ref "R12")
      (value "10k")
      (footprint "eagle-import:R0603")
      (libsource (lib "eagle-import") (part "RESISTOR-0603"))
    )
    (comp (ref "SJ1")
      (value "SOLDERJUMPER")
      (footprint "eagle-import:SOLDERJUMPER_ARROW_NOPASTE")
      (libsource (lib "eagle-import") (part "SOLDERJUMPER"))
    )
    (comp (ref "SW1")
      (value "BUTTON")
      (footprint "eagle-import:BUTTON_3_6_2.5")
      (libsource (lib "eagle-import") (part "BUTTON"))
    )
    (comp (ref "U1")
      (value "MCP1700T")
      (footprint "eagle-import:SOT-23")
      (libsource (lib "eagle-import") (part "MCP1700T"))
    )
    (comp (ref "U2")
      (value "PRTR5V0U2X")
      (footprint "eagle-import:PRTR5V0U2X")
      (libsource (lib "eagle-import") (part "PRTR5V0U2X"))
    )
    (comp (ref "U3")
      (value "STM32F303CC")
      (footprint "eagle-import:LQFP48")
      (libsource (lib "eagle-import") (part "STM32F303CC"))
    )
    (comp (ref "U4")
      (value "MB85RC256V")
      (footprint "eagle-import:SOP-8")
      (libsource (lib "eagle-import") (part "MB85RC256V"))
    )
    (comp (ref "U5")
      (value "INA219")
      (footprint "eagle-import:SOT23-8")
      (libsource (lib "eagle-import") (part "INA219"))
    )
    (comp (ref "U6")
      (value "TPS2552")
      (footprint "eagle-import:SOT-23-6P")
      (libsource (lib "eagle-import") (part "TPS2552"))
    )
    (comp (ref "X1")
      (value "USB-C-12P-INBOARD")
      (footprint "eagle-import:USB-C-12P-INBOARD")
      (libsource (lib "eagle-import") (part "CONTROLLER_USB-C-12PUSB-C-12P-INBOARD"))
    )
    (comp (ref "Y1")
      (value "8Mhz")
      (footprint "eagle-import:CRYSTAL-3.2X2.5")
      (libsource (lib "eagle-import") (part "CRYSTAL-4PIN-3.2X2.5"))
    )
  )
  (nets
    (net (code "1") (name "3.3V") (class "Default")
      (node (ref "C1") (pin "1") (pinfunction "1_1") (pintype "passive"))
      (node (ref "C15") (pin "2") (pinfunction "2_2") (pintype "passive"))
      (node (ref "C17") (pin "2") (pinfunction "2_2") (pintype "passive"))
      (node (ref "C2") (pin "1") (pinfunction "1_1") (pintype "passive"))
      (node (ref "C3") (pin "1") (pinfunction "1_1") (pintype "passive"))
      (node (ref "C4") (pin "1") (pinfunction "1_1") (pintype "passive"))
      (node (ref "C5") (pin "1") (pinfunction "1_1") (pintype "passive"))
      (node (ref "C6") (pin "1") (pinfunction "1_1") (pintype "passive"))
      (node (ref "C8") (pin "2") (pinfunction "2_2") (pintype "passive"))
      (node (ref "J1") (pin "VIN") (pinfunction "4_VIN") (pintype "passive"))
      (node (ref "PH1") (pin "6") (pinfunction "6_6") (pintype "passive"))
      (node (ref "R7") (pin "2") (pinfunction "2_2") (pintype "passive"))
      (node (ref "R8") (pin "2") (pinfunction "2_2") (pintype "passive"))
      (node (ref "SW1") (pin "P$2") (pinfunction "P$2_P$2") (pintype "bidirectional"))
      (node (ref "U1") (pin "2") (pinfunction "VO_2") (pintype "bidirectional"))
      (node (ref "U3") (pin "1") (pinfunction "VBAT_1") (pintype "bidirectional"))
      (node (ref "U3") (pin "24") (pinfunction "VCC_24") (pintype "bidirectional"))
      (node (ref "U3") (pin "36") (pinfunction "VCC1_36") (pintype "bidirectional"))
      (node (ref "U3") (pin "48") (pinfunction "VCC2_48") (pintype "bidirectional"))
      (node (ref "U3") (pin "9") (pinfunction "VCC/VDDA/VREF+_9") (pintype "bidirectional"))
      (node (ref "U4") (pin "8") (pinfunction "VCC_8") (pintype "bidirectional"))
      (node (ref "U5") (pin "4") (pinfunction "VCC_4") (pintype "bidirectional"))
    )
    (net (code "2") (name "BOOT0") (class "Default")
      (node (ref "C13") (pin "2") (pinfunction "2_2") (pintype "passive"))
      (node (ref "D2") (pin "C") (pinfunction "C_C") (pintype "passive"))
      (node (ref "PH1") (pin "3") (pinfunction "3_3") (pintype "passive"))
      (node (ref "R5") (pin "1") (pinfunction "1_1") (pintype "passive"))
      (node (ref "U3") (pin "44") (pinfunction "BOOT0_44") (pintype "bidirectional"))
    )
    (net (code "3") (name "CASE") (class "Default")
      (node (ref "D3") (pin "A") (pinfunction "A_A") (pintype "passive"))
      (node (ref "HOLE1") (pin "P$1") (pinfunction "CASE_P$1") (pintype "bidirectional"))
      (node (ref "HOLE1") (pin "P$2") (pinfunction "CASE_P$2") (pintype "bidirectional"))
      (node (ref "HOLE1") (pin "P$3") (pinfunction "CASE_P$3") (pintype "bidirectional"))
      (node (ref "HOLE2") (pin "P$1") (pinfunction "CASE_P$1") (pintype "bidirectional"))
      (node (ref "HOLE2") (pin "P$2") (pinfunction "CASE_P$2") (pintype "bidirectional"))
      (node (ref "HOLE2") (pin "P$3") (pinfunction "CASE_P$3") (pintype "bidirectional"))
      (node (ref "HOLE3") (pin "P$1") (pinfunction "CASE_P$1") (pintype "bidirectional"))
      (node (ref "HOLE3") (pin "P$2") (pinfunction "CASE_P$2") (pintype "bidirectional"))
      (node (ref "HOLE3") (pin "P$3") (pinfunction "CASE_P$3") (pintype "bidirectional"))
      (node (ref "HOLE4") (pin "P$1") (pinfunction "CASE_P$1") (pintype "bidirectional"))
      (node (ref "HOLE4") (pin "P$2") (pinfunction "CASE_P$2") (pintype "bidirectional"))
      (node (ref "HOLE4") (pin "P$3") (pinfunction "CASE_P$3") (pintype "bidirectional"))
      (node (ref "HOLE5") (pin "P$1") (pinfunction "CASE_P$1") (pintype "bidirectional"))
      (node (ref "HOLE5") (pin "P$2") (pinfunction "CASE_P$2") (pintype "bidirectional"))
      (node (ref "HOLE5") (pin "P$3") (pinfunction "CASE_P$3") (pintype "bidirectional"))
      (node (ref "HOLE6") (pin "P$1") (pinfunction "CASE_P$1") (pintype "bidirectional"))
      (node (ref "HOLE6") (pin "P$2") (pinfunction "CASE_P$2") (pintype "bidirectional"))
      (node (ref "HOLE6") (pin "P$3") (pinfunction "CASE_P$3") (pintype "bidirectional"))
    )
    (net (code "4") (name "COLUMN0") (class "Default")
      (node (ref "SW10") (pin "HOLE3") (pinfunction "P1_HOLE3") (pintype "bidirectional"))
      (node (ref "SW10") (pin "P$1") (pinfunction "P1_P$1") (pintype "bidirectional"))
      (node (ref "SW18") (pin "HOLE3") (pinfunction "P1_HOLE3") (pintype "bidirectional"))
      (node (ref "SW18") (pin "P$1") (pinfunction "P1_P$1") (pintype "bidirectional"))
      (node (ref "SW2") (pin "HOLE3") (pinfunction "P1_HOLE3") (pintype "bidirectional"))
      (node (ref "SW2") (pin "P$1") (pinfunction "P1_P$1") (pintype "bidirectional"))
      (node (ref "SW25") (pin "HOLE3") (pinfunction "P1_HOLE3") (pintype "bidirectional"))
      (node (ref "SW25") (pin "P$1") (pinfunction "P1_P$1") (pintype "bidirectional"))
      (node (ref "SW32") (pin "HOLE3") (pinfunction "P1_HOLE3") (pintype "bidirectional"))
      (node (ref "SW32") (pin "P$1") (pinfunction "P1_P$1") (pintype "bidirectional"))
      (node (ref "SW38") (pin "HOLE3") (pinfunction "P1_HOLE3") (pintype "bidirectional"))
      (node (ref "SW38") (pin "P$1") (pinfunction "P1_P$1") (pintype "bidirectional"))
      (node (ref "U3") (pin "15") (pinfunction "DAC1-OUT2/PA5_15") (pintype "bidirectional"))
    )
    (net (code "5") (name "COLUMN1") (class "Default")
      (node (ref "SW11") (pin "HOLE3") (pinfunction "P1_HOLE3") (pintype "bidirectional"))
      (node (ref "SW11") (pin "P$1") (pinfunction "P1_P$1") (pintype "bidirectional"))
      (node (ref "SW19") (pin "HOLE3") (pinfunction "P1_HOLE3") (pintype "bidirectional"))
      (node (ref "SW19") (pin "P$1") (pinfunction "P1_P$1") (pintype "bidirectional"))
      (node (ref "SW26") (pin "HOLE3") (pinfunction "P1_HOLE3") (pintype "bidirectional"))
      (node (ref "SW26") (pin "P$1") (pinfunction "P1_P$1") (pintype "bidirectional"))
      (node (ref "SW3") (pin "HOLE3") (pinfunction "P1_HOLE3") (pintype "bidirectional"))
      (node (ref "SW3") (pin "P$1") (pinfunction "P1_P$1") (pintype "bidirectional"))
      (node (ref "SW33") (pin "HOLE3") (pinfunction "P1_HOLE3") (pintype "bidirectional"))
      (node (ref "SW33") (pin "P$1") (pinfunction "P1_P$1") (pintype "bidirectional"))
      (node (ref "SW39") (pin "HOLE3") (pinfunction "P1_HOLE3") (pintype "bidirectional"))
      (node (ref "SW39") (pin "P$1") (pinfunction "P1_P$1") (pintype "bidirectional"))
      (node (ref "U3") (pin "16") (pinfunction "PA6_16") (pintype "bidirectional"))
    )
    (net (code "6") (name "COLUMN2") (class "Default")
      (node (ref "SW12") (pin "HOLE3") (pinfunction "P1_HOLE3") (pintype "bidirectional"))
      (node (ref "SW12") (pin "P$1") (pinfunction "P1_P$1") (pintype "bidirectional"))
      (node (ref "SW20") (pin "HOLE3") (pinfunction "P1_HOLE3") (pintype "bidirectional"))
      (node (ref "SW20") (pin "P$1") (pinfunction "P1_P$1") (pintype "bidirectional"))
      (node (ref "SW27") (pin "HOLE3") (pinfunction "P1_HOLE3") (pintype "bidirectional"))
      (node (ref "SW27") (pin "P$1") (pinfunction "P1_P$1") (pintype "bidirectional"))
      (node (ref "SW34") (pin "HOLE3") (pinfunction "P1_HOLE3") (pintype "bidirectional"))
      (node (ref "SW34") (pin "P$1") (pinfunction "P1_P$1") (pintype "bidirectional"))
      (node (ref "SW4") (pin "HOLE3") (pinfunction "P1_HOLE3") (pintype "bidirectional"))
      (node (ref "SW4") (pin "P$1") (pinfunction "P1_P$1") (pintype "bidirectional"))
      (node (ref "SW40") (pin "HOLE3") (pinfunction "P1_HOLE3") (pintype "bidirectional"))
      (node (ref "SW40") (pin "P$1") (pinfunction "P1_P$1") (pintype "bidirectional"))
      (node (ref "U3") (pin "17") (pinfunction "PA7_17") (pintype "bidirectional"))
    )
    (net (code "7") (name "COLUMN3") (class "Default")
      (node (ref "SW13") (pin "HOLE3") (pinfunction "P1_HOLE3") (pintype "bidirectional"))
      (node (ref "SW13") (pin "P$1") (pinfunction "P1_P$1") (pintype "bidirectional"))
      (node (ref "SW21") (pin "HOLE3") (pinfunction "P1_HOLE3") (pintype "bidirectional"))
      (node (ref "SW21") (pin "P$1") (pinfunction "P1_P$1") (pintype "bidirectional"))
      (node (ref "SW28") (pin "HOLE3") (pinfunction "P1_HOLE3") (pintype "bidirectional"))
      (node (ref "SW28") (pin "P$1") (pinfunction "P1_P$1") (pintype "bidirectional"))
      (node (ref "SW35") (pin "HOLE3") (pinfunction "P1_HOLE3") (pintype "bidirectional"))
      (node (ref "SW35") (pin "P$1") (pinfunction "P1_P$1") (pintype "bidirectional"))
      (node (ref "SW41") (pin "HOLE3") (pinfunction "P1_HOLE3") (pintype "bidirectional"))
      (node (ref "SW41") (pin "P$1") (pinfunction "P1_P$1") (pintype "bidirectional"))
      (node (ref "SW5") (pin "HOLE3") (pinfunction "P1_HOLE3") (pintype "bidirectional"))
      (node (ref "SW5") (pin "P$1") (pinfunction "P1_P$1") (pintype "bidirectional"))
      (node (ref "U3") (pin "18") (pinfunction "PB0_18") (pintype "bidirectional"))
    )
    (net (code "8") (name "COLUMN4") (class "Default")
      (node (ref "SW14") (pin "HOLE3") (pinfunction "P1_HOLE3") (pintype "bidirectional"))
      (node (ref "SW14") (pin "P$1") (pinfunction "P1_P$1") (pintype "bidirectional"))
      (node (ref "SW22") (pin "HOLE3") (pinfunction "P1_HOLE3") (pintype "bidirectional"))
      (node (ref "SW22") (pin "P$1") (pinfunction "P1_P$1") (pintype "bidirectional"))
      (node (ref "SW29") (pin "HOLE3") (pinfunction "P1_HOLE3") (pintype "bidirectional"))
      (node (ref "SW29") (pin "P$1") (pinfunction "P1_P$1") (pintype "bidirectional"))
      (node (ref "SW36") (pin "HOLE3") (pinfunction "P1_HOLE3") (pintype "bidirectional"))
      (node (ref "SW36") (pin "P$1") (pinfunction "P1_P$1") (pintype "bidirectional"))
      (node (ref "SW6") (pin "HOLE3") (pinfunction "P1_HOLE3") (pintype "bidirectional"))
      (node (ref "SW6") (pin "P$1") (pinfunction "P1_P$1") (pintype "bidirectional"))
      (node (ref "U3") (pin "19") (pinfunction "PB1_19") (pintype "bidirectional"))
    )
    (net (code "9") (name "COLUMN5") (class "Default")
      (node (ref "SW15") (pin "HOLE3") (pinfunction "P1_HOLE3") (pintype "bidirectional"))
      (node (ref "SW15") (pin "P$1") (pinfunction "P1_P$1") (pintype "bidirectional"))
      (node (ref "SW23") (pin "HOLE3") (pinfunction "P1_HOLE3") (pintype "bidirectional"))
      (node (ref "SW23") (pin "P$1") (pinfunction "P1_P$1") (pintype "bidirectional"))
      (node (ref "SW30") (pin "HOLE3") (pinfunction "P1_HOLE3") (pintype "bidirectional"))
      (node (ref "SW30") (pin "P$1") (pinfunction "P1_P$1") (pintype "bidirectional"))
      (node (ref "SW37") (pin "HOLE3") (pinfunction "P1_HOLE3") (pintype "bidirectional"))
      (node (ref "SW37") (pin "P$1") (pinfunction "P1_P$1") (pintype "bidirectional"))
      (node (ref "SW42") (pin "HOLE3") (pinfunction "P1_HOLE3") (pintype "bidirectional"))
      (node (ref "SW42") (pin "P$1") (pinfunction "P1_P$1") (pintype "bidirectional"))
      (node (ref "SW7") (pin "HOLE3") (pinfunction "P1_HOLE3") (pintype "bidirectional"))
      (node (ref "SW7") (pin "P$1") (pinfunction "P1_P$1") (pintype "bidirectional"))
      (node (ref "U3") (pin "21") (pinfunction "PB10_21") (pintype "bidirectional"))
    )
    (net (code "10") (name "COLUMN6") (class "Default")
      (node (ref "SW16") (pin "HOLE3") (pinfunction "P1_HOLE3") (pintype "bidirectional"))
      (node (ref "SW16") (pin "P$1") (pinfunction "P1_P$1") (pintype "bidirectional"))
      (node (ref "SW8") (pin "HOLE3") (pinfunction "P1_HOLE3") (pintype "bidirectional"))
      (node (ref "SW8") (pin "P$1") (pinfunction "P1_P$1") (pintype "bidirectional"))
      (node (ref "U3") (pin "22") (pinfunction "PB11_22") (pintype "bidirectional"))
    )
    (net (code "11") (name "COLUMN7") (class "Default")
      (node (ref "SW17") (pin "HOLE3") (pinfunction "P1_HOLE3") (pintype "bidirectional"))
      (node (ref "SW17") (pin "P$1") (pinfunction "P1_P$1") (pintype "bidirectional"))
      (node (ref "SW24") (pin "HOLE3") (pinfunction "P1_HOLE3") (pintype "bidirectional"))
      (node (ref "SW24") (pin "P$1") (pinfunction "P1_P$1") (pintype "bidirectional"))
      (node (ref "SW31") (pin "HOLE3") (pinfunction "P1_HOLE3") (pintype "bidirectional"))
      (node (ref "SW31") (pin "P$1") (pinfunction "P1_P$1") (pintype "bidirectional"))
      (node (ref "SW9") (pin "HOLE3") (pinfunction "P1_HOLE3") (pintype "bidirectional"))
      (node (ref "SW9") (pin "P$1") (pinfunction "P1_P$1") (pintype "bidirectional"))
      (node (ref "U3") (pin "25") (pinfunction "PB12_25") (pintype "bidirectional"))
    )
    (net (code "12") (name "D+") (class "Default")
      (node (ref "R2") (pin "2") (pinfunction "2_2") (pintype "passive"))
      (node (ref "U2") (pin "2") (pinfunction "2_2") (pintype "bidirectional"))
      (node (ref "U3") (pin "33") (pinfunction "PA12/USB_DP_33") (pintype "bidirectional"))
      (node (ref "X1") (pin "DP1") (pinfunction "DP1_DP1") (pintype "passive"))
      (node (ref "X1") (pin "DP2") (pinfunction "DP2_DP2") (pintype "passive"))
    )
    (net (code "13") (name "D-") (class "Default")
      (node (ref "U2") (pin "3") (pinfunction "3_3") (pintype "bidirectional"))
      (node (ref "U3") (pin "32") (pinfunction "PA11/USB_DM_32") (pintype "bidirectional"))
      (node (ref "X1") (pin "DN1") (pinfunction "DN1_DN1") (pintype "passive"))
      (node (ref "X1") (pin "DN2") (pinfunction "DN2_DN2") (pintype "passive"))
    )
    (net (code "14") (name "GND") (class "Default")
      (node (ref "C1") (pin "2") (pinfunction "2_2") (pintype "passive"))
      (node (ref "C10") (pin "1") (pinfunction "1_1") (pintype "passive"))
      (node (ref "C11") (pin "1") (pinfunction "1_1") (pintype "passive"))
      (node (ref "C12") (pin "2") (pinfunction "2_2") (pintype "passive"))
      (node (ref "C13") (pin "1") (pinfunction "1_1") (pintype "passive"))
      (node (ref "C14") (pin "1") (pinfunction "1_1") (pintype "passive"))
      (node (ref "C15") (pin "1") (pinfunction "1_1") (pintype "passive"))
      (node (ref "C16") (pin "2") (pinfunction "2_2") (pintype "passive"))
      (node (ref "C17") (pin "1") (pinfunction "1_1") (pintype "passive"))
      (node (ref "C18") (pin "1") (pinfunction "1_1") (pintype "passive"))
      (node (ref "C19") (pin "1") (pinfunction "1_1") (pintype "passive"))
      (node (ref "C2") (pin "2") (pinfunction "2_2") (pintype "passive"))
      (node (ref "C20") (pin "1") (pinfunction "1_1") (pintype "passive"))
      (node (ref "C21") (pin "1") (pinfunction "1_1") (pintype "passive"))
      (node (ref "C22") (pin "1") (pinfunction "1_1") (pintype "passive"))
      (node (ref "C23") (pin "1") (pinfunction "1_1") (pintype "passive"))
      (node (ref "C24") (pin "1") (pinfunction "1_1") (pintype "passive"))
      (node (ref "C25") (pin "1") (pinfunction "1_1") (pintype "passive"))
      (node (ref "C26") (pin "1") (pinfunction "1_1") (pintype "passive"))
      (node (ref "C27") (pin "1") (pinfunction "1_1") (pintype "passive"))
      (node (ref "C28") (pin "1") (pinfunction "1_1") (pintype "passive"))
      (node (ref "C29") (pin "1") (pinfunction "1_1") (pintype "passive"))
      (node (ref "C3") (pin "2") (pinfunction "2_2") (pintype "passive"))
      (node (ref "C30") (pin "1") (pinfunction "1_1") (pintype "passive"))
      (node (ref "C31") (pin "1") (pinfunction "1_1") (pintype "passive"))
      (node (ref "C32") (pin "1") (pinfunction "1_1") (pintype "passive"))
      (node (ref "C33") (pin "1") (pinfunction "1_1") (pintype "passive"))
      (node (ref "C34") (pin "1") (pinfunction "1_1") (pintype "passive"))
      (node (ref "C35") (pin "1") (pinfunction "1_1") (pintype "passive"))
      (node (ref "C36") (pin "1") (pinfunction "1_1") (pintype "passive"))
      (node (ref "C37") (pin "1") (pinfunction "1_1") (pintype "passive"))
      (node (ref "C38") (pin "1") (pinfunction "1_1") (pintype "passive"))
      (node (ref "C39") (pin "1") (pinfunction "1_1") (pintype "passive"))
      (node (ref "C4") (pin "2") (pinfunction "2_2") (pintype "passive"))
      (node (ref "C40") (pin "1") (pinfunction "1_1") (pintype "passive"))
      (node (ref "C41") (pin "1") (pinfunction "1_1") (pintype "passive"))
      (node (ref "C42") (pin "1") (pinfunction "1_1") (pintype "passive"))
      (node (ref "C43") (pin "1") (pinfunction "1_1") (pintype "passive"))
      (node (ref "C44") (pin "1") (pinfunction "1_1") (pintype "passive"))
      (node (ref "C45") (pin "1") (pinfunction "1_1") (pintype "passive"))
      (node (ref "C46") (pin "1") (pinfunction "1_1") (pintype "passive"))
      (node (ref "C47") (pin "1") (pinfunction "1_1") (pintype "passive"))
      (node (ref "C48") (pin "1") (pinfunction "1_1") (pintype "passive"))
      (node (ref "C49") (pin "1") (pinfunction "1_1") (pintype "passive"))
      (node (ref "C5") (pin "2") (pinfunction "2_2") (pintype "passive"))
      (node (ref "C50") (pin "1") (pinfunction "1_1") (pintype "passive"))
      (node (ref "C51") (pin "1") (pinfunction "1_1") (pintype "passive"))
      (node (ref "C52") (pin "1") (pinfunction "1_1") (pintype "passive"))
      (node (ref "C6") (pin "2") (pinfunction "2_2") (pintype "passive"))
      (node (ref "C7") (pin "1") (pinfunction "1_1") (pintype "passive"))
      (node (ref "C8") (pin "1") (pinfunction "1_1") (pintype "passive"))
      (node (ref "C9") (pin "2") (pinfunction "2_2") (pintype "passive"))
      (node (ref "D1") (pin "A") (pinfunction "A_A") (pintype "passive"))
      (node (ref "J1") (pin "GND") (pinfunction "3_GND") (pintype "passive"))
      (node (ref "LED1") (pin "GND") (pinfunction "GND_GND") (pintype "power_in"))
      (node (ref "LED10") (pin "GND") (pinfunction "GND_GND") (pintype "power_in"))
      (node (ref "LED11") (pin "GND") (pinfunction "GND_GND") (pintype "power_in"))
      (node (ref "LED12") (pin "GND") (pinfunction "GND_GND") (pintype "power_in"))
      (node (ref "LED13") (pin "GND") (pinfunction "GND_GND") (pintype "power_in"))
      (node (ref "LED14") (pin "GND") (pinfunction "GND_GND") (pintype "power_in"))
      (node (ref "LED15") (pin "GND") (pinfunction "GND_GND") (pintype "power_in"))
      (node (ref "LED16") (pin "GND") (pinfunction "GND_GND") (pintype "power_in"))
      (node (ref "LED17") (pin "GND") (pinfunction "GND_GND") (pintype "power_in"))
      (node (ref "LED18") (pin "GND") (pinfunction "GND_GND") (pintype "power_in"))
      (node (ref "LED19") (pin "GND") (pinfunction "GND_GND") (pintype "power_in"))
      (node (ref "LED2") (pin "GND") (pinfunction "GND_GND") (pintype "power_in"))
      (node (ref "LED20") (pin "GND") (pinfunction "GND_GND") (pintype "power_in"))
      (node (ref "LED21") (pin "GND") (pinfunction "GND_GND") (pintype "power_in"))
      (node (ref "LED22") (pin "GND") (pinfunction "GND_GND") (pintype "power_in"))
      (node (ref "LED23") (pin "GND") (pinfunction "GND_GND") (pintype "power_in"))
      (node (ref "LED24") (pin "GND") (pinfunction "GND_GND") (pintype "power_in"))
      (node (ref "LED25") (pin "GND") (pinfunction "GND_GND") (pintype "power_in"))
      (node (ref "LED26") (pin "GND") (pinfunction "GND_GND") (pintype "power_in"))
      (node (ref "LED27") (pin "GND") (pinfunction "GND_GND") (pintype "power_in"))
      (node (ref "LED28") (pin "GND") (pinfunction "GND_GND") (pintype "power_in"))
      (node (ref "LED29") (pin "GND") (pinfunction "GND_GND") (pintype "power_in"))
      (node (ref "LED3") (pin "GND") (pinfunction "GND_GND") (pintype "power_in"))
      (node (ref "LED30") (pin "GND") (pinfunction "GND_GND") (pintype "power_in"))
      (node (ref "LED31") (pin "GND") (pinfunction "GND_GND") (pintype "power_in"))
      (node (ref "LED32") (pin "GND") (pinfunction "GND_GND") (pintype "power_in"))
      (node (ref "LED33") (pin "GND") (pinfunction "GND_GND") (pintype "power_in"))
      (node (ref "LED34") (pin "GND") (pinfunction "GND_GND") (pintype "power_in"))
      (node (ref "LED35") (pin "GND") (pinfunction "GND_GND") (pintype "power_in"))
      (node (ref "LED36") (pin "GND") (pinfunction "GND_GND") (pintype "power_in"))
      (node (ref "LED37") (pin "GND") (pinfunction "GND_GND") (pintype "power_in"))
      (node (ref "LED38") (pin "GND") (pinfunction "GND_GND") (pintype "power_in"))
      (node (ref "LED39") (pin "GND") (pinfunction "GND_GND") (pintype "power_in"))
      (node (ref "LED4") (pin "GND") (pinfunction "GND_GND") (pintype "power_in"))
      (node (ref "LED40") (pin "GND") (pinfunction "GND_GND") (pintype "power_in"))
      (node (ref "LED41") (pin "GND") (pinfunction "GND_GND") (pintype "power_in"))
      (node (ref "LED5") (pin "GND") (pinfunction "GND_GND") (pintype "power_in"))
      (node (ref "LED6") (pin "GND") (pinfunction "GND_GND") (pintype "power_in"))
      (node (ref "LED7") (pin "GND") (pinfunction "GND_GND") (pintype "power_in"))
      (node (ref "LED8") (pin "GND") (pinfunction "GND_GND") (pintype "power_in"))
      (node (ref "LED9") (pin "GND") (pinfunction "GND_GND") (pintype "power_in"))
      (node (ref "PH1") (pin "1") (pinfunction "1_1") (pintype "passive"))
      (node (ref "Q1") (pin "2") (pinfunction "E_2") (pintype "bidirectional"))
      (node (ref "R1") (pin "2") (pinfunction "2_2") (pintype "passive"))
      (node (ref "R11") (pin "1") (pinfunction "1_1") (pintype "passive"))
      (node (ref "R12") (pin "1") (pinfunction "1_1") (pintype "passive"))
      (node (ref "R3") (pin "2") (pinfunction "2_2") (pintype "passive"))
      (node (ref "R4") (pin "2") (pinfunction "2_2") (pintype "passive"))
      (node (ref "R5") (pin "2") (pinfunction "2_2") (pintype "passive"))
      (node (ref "R9") (pin "2") (pinfunction "2_2") (pintype "passive"))
      (node (ref "SW10") (pin "HOLE1") (pinfunction "HOLE_HOLE1") (pintype "bidirectional"))
      (node (ref "SW10") (pin "HOLE4") (pinfunction "HOLE_HOLE4") (pintype "bidirectional"))
      (node (ref "SW10") (pin "HOLE5") (pinfunction "HOLE_HOLE5") (pintype "bidirectional"))
      (node (ref "SW11") (pin "HOLE1") (pinfunction "HOLE_HOLE1") (pintype "bidirectional"))
      (node (ref "SW11") (pin "HOLE4") (pinfunction "HOLE_HOLE4") (pintype "bidirectional"))
      (node (ref "SW11") (pin "HOLE5") (pinfunction "HOLE_HOLE5") (pintype "bidirectional"))
      (node (ref "SW12") (pin "HOLE1") (pinfunction "HOLE_HOLE1") (pintype "bidirectional"))
      (node (ref "SW12") (pin "HOLE4") (pinfunction "HOLE_HOLE4") (pintype "bidirectional"))
      (node (ref "SW12") (pin "HOLE5") (pinfunction "HOLE_HOLE5") (pintype "bidirectional"))
      (node (ref "SW13") (pin "HOLE1") (pinfunction "HOLE_HOLE1") (pintype "bidirectional"))
      (node (ref "SW13") (pin "HOLE4") (pinfunction "HOLE_HOLE4") (pintype "bidirectional"))
      (node (ref "SW13") (pin "HOLE5") (pinfunction "HOLE_HOLE5") (pintype "bidirectional"))
      (node (ref "SW14") (pin "HOLE1") (pinfunction "HOLE_HOLE1") (pintype "bidirectional"))
      (node (ref "SW14") (pin "HOLE4") (pinfunction "HOLE_HOLE4") (pintype "bidirectional"))
      (node (ref "SW14") (pin "HOLE5") (pinfunction "HOLE_HOLE5") (pintype "bidirectional"))
      (node (ref "SW15") (pin "HOLE1") (pinfunction "HOLE_HOLE1") (pintype "bidirectional"))
      (node (ref "SW15") (pin "HOLE4") (pinfunction "HOLE_HOLE4") (pintype "bidirectional"))
      (node (ref "SW15") (pin "HOLE5") (pinfunction "HOLE_HOLE5") (pintype "bidirectional"))
      (node (ref "SW16") (pin "HOLE1") (pinfunction "HOLE_HOLE1") (pintype "bidirectional"))
      (node (ref "SW16") (pin "HOLE4") (pinfunction "HOLE_HOLE4") (pintype "bidirectional"))
      (node (ref "SW16") (pin "HOLE5") (pinfunction "HOLE_HOLE5") (pintype "bidirectional"))
      (node (ref "SW17") (pin "HOLE1") (pinfunction "HOLE_HOLE1") (pintype "bidirectional"))
      (node (ref "SW17") (pin "HOLE4") (pinfunction "HOLE_HOLE4") (pintype "bidirectional"))
      (node (ref "SW17") (pin "HOLE5") (pinfunction "HOLE_HOLE5") (pintype "bidirectional"))
      (node (ref "SW18") (pin "HOLE1") (pinfunction "HOLE_HOLE1") (pintype "bidirectional"))
      (node (ref "SW18") (pin "HOLE4") (pinfunction "HOLE_HOLE4") (pintype "bidirectional"))
      (node (ref "SW18") (pin "HOLE5") (pinfunction "HOLE_HOLE5") (pintype "bidirectional"))
      (node (ref "SW19") (pin "HOLE1") (pinfunction "HOLE_HOLE1") (pintype "bidirectional"))
      (node (ref "SW19") (pin "HOLE4") (pinfunction "HOLE_HOLE4") (pintype "bidirectional"))
      (node (ref "SW19") (pin "HOLE5") (pinfunction "HOLE_HOLE5") (pintype "bidirectional"))
      (node (ref "SW2") (pin "HOLE1") (pinfunction "HOLE_HOLE1") (pintype "bidirectional"))
      (node (ref "SW2") (pin "HOLE4") (pinfunction "HOLE_HOLE4") (pintype "bidirectional"))
      (node (ref "SW2") (pin "HOLE5") (pinfunction "HOLE_HOLE5") (pintype "bidirectional"))
      (node (ref "SW20") (pin "HOLE1") (pinfunction "HOLE_HOLE1") (pintype "bidirectional"))
      (node (ref "SW20") (pin "HOLE4") (pinfunction "HOLE_HOLE4") (pintype "bidirectional"))
      (node (ref "SW20") (pin "HOLE5") (pinfunction "HOLE_HOLE5") (pintype "bidirectional"))
      (node (ref "SW21") (pin "HOLE1") (pinfunction "HOLE_HOLE1") (pintype "bidirectional"))
      (node (ref "SW21") (pin "HOLE4") (pinfunction "HOLE_HOLE4") (pintype "bidirectional"))
      (node (ref "SW21") (pin "HOLE5") (pinfunction "HOLE_HOLE5") (pintype "bidirectional"))
      (node (ref "SW22") (pin "HOLE1") (pinfunction "HOLE_HOLE1") (pintype "bidirectional"))
      (node (ref "SW22") (pin "HOLE4") (pinfunction "HOLE_HOLE4") (pintype "bidirectional"))
      (node (ref "SW22") (pin "HOLE5") (pinfunction "HOLE_HOLE5") (pintype "bidirectional"))
      (node (ref "SW23") (pin "HOLE1") (pinfunction "HOLE_HOLE1") (pintype "bidirectional"))
      (node (ref "SW23") (pin "HOLE4") (pinfunction "HOLE_HOLE4") (pintype "bidirectional"))
      (node (ref "SW23") (pin "HOLE5") (pinfunction "HOLE_HOLE5") (pintype "bidirectional"))
      (node (ref "SW24") (pin "HOLE1") (pinfunction "HOLE_HOLE1") (pintype "bidirectional"))
      (node (ref "SW24") (pin "HOLE4") (pinfunction "HOLE_HOLE4") (pintype "bidirectional"))
      (node (ref "SW24") (pin "HOLE5") (pinfunction "HOLE_HOLE5") (pintype "bidirectional"))
      (node (ref "SW25") (pin "HOLE1") (pinfunction "HOLE_HOLE1") (pintype "bidirectional"))
      (node (ref "SW25") (pin "HOLE4") (pinfunction "HOLE_HOLE4") (pintype "bidirectional"))
      (node (ref "SW25") (pin "HOLE5") (pinfunction "HOLE_HOLE5") (pintype "bidirectional"))
      (node (ref "SW26") (pin "HOLE1") (pinfunction "HOLE_HOLE1") (pintype "bidirectional"))
      (node (ref "SW26") (pin "HOLE4") (pinfunction "HOLE_HOLE4") (pintype "bidirectional"))
      (node (ref "SW26") (pin "HOLE5") (pinfunction "HOLE_HOLE5") (pintype "bidirectional"))
      (node (ref "SW27") (pin "HOLE1") (pinfunction "HOLE_HOLE1") (pintype "bidirectional"))
      (node (ref "SW27") (pin "HOLE4") (pinfunction "HOLE_HOLE4") (pintype "bidirectional"))
      (node (ref "SW27") (pin "HOLE5") (pinfunction "HOLE_HOLE5") (pintype "bidirectional"))
      (node (ref "SW28") (pin "HOLE1") (pinfunction "HOLE_HOLE1") (pintype "bidirectional"))
      (node (ref "SW28") (pin "HOLE4") (pinfunction "HOLE_HOLE4") (pintype "bidirectional"))
      (node (ref "SW28") (pin "HOLE5") (pinfunction "HOLE_HOLE5") (pintype "bidirectional"))
      (node (ref "SW29") (pin "HOLE1") (pinfunction "HOLE_HOLE1") (pintype "bidirectional"))
      (node (ref "SW29") (pin "HOLE4") (pinfunction "HOLE_HOLE4") (pintype "bidirectional"))
      (node (ref "SW29") (pin "HOLE5") (pinfunction "HOLE_HOLE5") (pintype "bidirectional"))
      (node (ref "SW3") (pin "HOLE1") (pinfunction "HOLE_HOLE1") (pintype "bidirectional"))
      (node (ref "SW3") (pin "HOLE4") (pinfunction "HOLE_HOLE4") (pintype "bidirectional"))
      (node (ref "SW3") (pin "HOLE5") (pinfunction "HOLE_HOLE5") (pintype "bidirectional"))
      (node (ref "SW30") (pin "HOLE1") (pinfunction "HOLE_HOLE1") (pintype "bidirectional"))
      (node (ref "SW30") (pin "HOLE4") (pinfunction "HOLE_HOLE4") (pintype "bidirectional"))
      (node (ref "SW30") (pin "HOLE5") (pinfunction "HOLE_HOLE5") (pintype "bidirectional"))
      (node (ref "SW31") (pin "HOLE1") (pinfunction "HOLE_HOLE1") (pintype "bidirectional"))
      (node (ref "SW31") (pin "HOLE4") (pinfunction "HOLE_HOLE4") (pintype "bidirectional"))
      (node (ref "SW31") (pin "HOLE5") (pinfunction "HOLE_HOLE5") (pintype "bidirectional"))
      (node (ref "SW32") (pin "HOLE1") (pinfunction "HOLE_HOLE1") (pintype "bidirectional"))
      (node (ref "SW32") (pin "HOLE4") (pinfunction "HOLE_HOLE4") (pintype "bidirectional"))
      (node (ref "SW32") (pin "HOLE5") (pinfunction "HOLE_HOLE5") (pintype "bidirectional"))
      (node (ref "SW32") (pin "HOLE6") (pinfunction "HOLE_HOLE6") (pintype "bidirectional"))
      (node (ref "SW32") (pin "HOLE7") (pinfunction "HOLE_HOLE7") (pintype "bidirectional"))
      (node (ref "SW32") (pin "HOLE8") (pinfunction "HOLE_HOLE8") (pintype "bidirectional"))
      (node (ref "SW32") (pin "HOLE9") (pinfunction "HOLE_HOLE9") (pintype "bidirectional"))
      (node (ref "SW33") (pin "HOLE1") (pinfunction "HOLE_HOLE1") (pintype "bidirectional"))
      (node (ref "SW33") (pin "HOLE4") (pinfunction "HOLE_HOLE4") (pintype "bidirectional"))
      (node (ref "SW33") (pin "HOLE5") (pinfunction "HOLE_HOLE5") (pintype "bidirectional"))
      (node (ref "SW34") (pin "HOLE1") (pinfunction "HOLE_HOLE1") (pintype "bidirectional"))
      (node (ref "SW34") (pin "HOLE4") (pinfunction "HOLE_HOLE4") (pintype "bidirectional"))
      (node (ref "SW34") (pin "HOLE5") (pinfunction "HOLE_HOLE5") (pintype "bidirectional"))
      (node (ref "SW35") (pin "HOLE1") (pinfunction "HOLE_HOLE1") (pintype "bidirectional"))
      (node (ref "SW35") (pin "HOLE4") (pinfunction "HOLE_HOLE4") (pintype "bidirectional"))
      (node (ref "SW35") (pin "HOLE5") (pinfunction "HOLE_HOLE5") (pintype "bidirectional"))
      (node (ref "SW36") (pin "HOLE1") (pinfunction "HOLE_HOLE1") (pintype "bidirectional"))
      (node (ref "SW36") (pin "HOLE4") (pinfunction "HOLE_HOLE4") (pintype "bidirectional"))
      (node (ref "SW36") (pin "HOLE5") (pinfunction "HOLE_HOLE5") (pintype "bidirectional"))
      (node (ref "SW37") (pin "HOLE1") (pinfunction "HOLE_HOLE1") (pintype "bidirectional"))
      (node (ref "SW37") (pin "HOLE4") (pinfunction "HOLE_HOLE4") (pintype "bidirectional"))
      (node (ref "SW37") (pin "HOLE5") (pinfunction "HOLE_HOLE5") (pintype "bidirectional"))
      (node (ref "SW38") (pin "HOLE1") (pinfunction "HOLE_HOLE1") (pintype "bidirectional"))
      (node (ref "SW38") (pin "HOLE4") (pinfunction "HOLE_HOLE4") (pintype "bidirectional"))
      (node (ref "SW38") (pin "HOLE5") (pinfunction "HOLE_HOLE5") (pintype "bidirectional"))
      (node (ref "SW39") (pin "HOLE1") (pinfunction "HOLE_HOLE1") (pintype "bidirectional"))
      (node (ref "SW39") (pin "HOLE4") (pinfunction "HOLE_HOLE4") (pintype "bidirectional"))
      (node (ref "SW39") (pin "HOLE5") (pinfunction "HOLE_HOLE5") (pintype "bidirectional"))
      (node (ref "SW4") (pin "HOLE1") (pinfunction "HOLE_HOLE1") (pintype "bidirectional"))
      (node (ref "SW4") (pin "HOLE4") (pinfunction "HOLE_HOLE4") (pintype "bidirectional"))
      (node (ref "SW4") (pin "HOLE5") (pinfunction "HOLE_HOLE5") (pintype "bidirectional"))
      (node (ref "SW40") (pin "HOLE1") (pinfunction "HOLE_HOLE1") (pintype "bidirectional"))
      (node (ref "SW40") (pin "HOLE4") (pinfunction "HOLE_HOLE4") (pintype "bidirectional"))
      (node (ref "SW40") (pin "HOLE5") (pinfunction "HOLE_HOLE5") (pintype "bidirectional"))
      (node (ref "SW41") (pin "HOLE1") (pinfunction "HOLE_HOLE1") (pintype "bidirectional"))
      (node (ref "SW41") (pin "HOLE4") (pinfunction "HOLE_HOLE4") (pintype "bidirectional"))
      (node (ref "SW41") (pin "HOLE5") (pinfunction "HOLE_HOLE5") (pintype "bidirectional"))
      (node (ref "SW41") (pin "HOLE6") (pinfunction "HOLE_HOLE6") (pintype "bidirectional"))
      (node (ref "SW41") (pin "HOLE7") (pinfunction "HOLE_HOLE7") (pintype "bidirectional"))
      (node (ref "SW41") (pin "HOLE8") (pinfunction "HOLE_HOLE8") (pintype "bidirectional"))
      (node (ref "SW41") (pin "HOLE9") (pinfunction "HOLE_HOLE9") (pintype "bidirectional"))
      (node (ref "SW42") (pin "HOLE1") (pinfunction "HOLE_HOLE1") (pintype "bidirectional"))
      (node (ref "SW42") (pin "HOLE4") (pinfunction "HOLE_HOLE4") (pintype "bidirectional"))
      (node (ref "SW42") (pin "HOLE5") (pinfunction "HOLE_HOLE5") (pintype "bidirectional"))
      (node (ref "SW5") (pin "HOLE1") (pinfunction "HOLE_HOLE1") (pintype "bidirectional"))
      (node (ref "SW5") (pin "HOLE4") (pinfunction "HOLE_HOLE4") (pintype "bidirectional"))
      (node (ref "SW5") (pin "HOLE5") (pinfunction "HOLE_HOLE5") (pintype "bidirectional"))
      (node (ref "SW6") (pin "HOLE1") (pinfunction "HOLE_HOLE1") (pintype "bidirectional"))
      (node (ref "SW6") (pin "HOLE4") (pinfunction "HOLE_HOLE4") (pintype "bidirectional"))
      (node (ref "SW6") (pin "HOLE5") (pinfunction "HOLE_HOLE5") (pintype "bidirectional"))
      (node (ref "SW7") (pin "HOLE1") (pinfunction "HOLE_HOLE1") (pintype "bidirectional"))
      (node (ref "SW7") (pin "HOLE4") (pinfunction "HOLE_HOLE4") (pintype "bidirectional"))
      (node (ref "SW7") (pin "HOLE5") (pinfunction "HOLE_HOLE5") (pintype "bidirectional"))
      (node (ref "SW8") (pin "HOLE1") (pinfunction "HOLE_HOLE1") (pintype "bidirectional"))
      (node (ref "SW8") (pin "HOLE4") (pinfunction "HOLE_HOLE4") (pintype "bidirectional"))
      (node (ref "SW8") (pin "HOLE5") (pinfunction "HOLE_HOLE5") (pintype "bidirectional"))
      (node (ref "SW9") (pin "HOLE1") (pinfunction "HOLE_HOLE1") (pintype "bidirectional"))
      (node (ref "SW9") (pin "HOLE4") (pinfunction "HOLE_HOLE4") (pintype "bidirectional"))
      (node (ref "SW9") (pin "HOLE5") (pinfunction "HOLE_HOLE5") (pintype "bidirectional"))
      (node (ref "U1") (pin "1") (pinfunction "GND_1") (pintype "bidirectional"))
      (node (ref "U2") (pin "1") (pinfunction "1_1") (pintype "bidirectional"))
      (node (ref "U3") (pin "23") (pinfunction "GND_23") (pintype "bidirectional"))
      (node (ref "U3") (pin "35") (pinfunction "GND1_35") (pintype "bidirectional"))
      (node (ref "U3") (pin "47") (pinfunction "GND2_47") (pintype "bidirectional"))
      (node (ref "U3") (pin "8") (pinfunction "GND/VSSA/VREF-_8") (pintype "bidirectional"))
      (node (ref "U4") (pin "4") (pinfunction "GND_4") (pintype "bidirectional"))
      (node (ref "U5") (pin "3") (pinfunction "GND_3") (pintype "bidirectional"))
      (node (ref "U6") (pin "2") (pinfunction "GND_2") (pintype "bidirectional"))
      (node (ref "X1") (pin "GND1") (pinfunction "GND1_GND1") (pintype "passive"))
      (node (ref "X1") (pin "GND2") (pinfunction "GND2_GND2") (pintype "input"))
      (node (ref "Y1") (pin "2") (pinfunction "GND_2") (pintype "bidirectional"))
      (node (ref "Y1") (pin "4") (pinfunction "GND_4") (pintype "bidirectional"))
    )
    (net (code "15") (name "LED_DATA") (class "Default")
      (node (ref "LED41") (pin "DIN") (pinfunction "DI_DIN") (pintype "input"))
      (node (ref "U3") (pin "14") (pinfunction "DAC1-OUT1/PA4_14") (pintype "bidirectional"))
    )
    (net (code "16") (name "LED_ENABLE") (class "Default")
      (node (ref "R12") (pin "2") (pinfunction "2_2") (pintype "passive"))
      (node (ref "U3") (pin "11") (pinfunction "PA1_11") (pintype "bidirectional"))
      (node (ref "U6") (pin "3") (pinfunction "EN_3") (pintype "bidirectional"))
    )
    (net (code "17") (name "LED_FAULT") (class "Default")
      (node (ref "R6") (pin "1") (pinfunction "1_1") (pintype "passive"))
      (node (ref "U3") (pin "12") (pinfunction "PA2_12") (pintype "bidirectional"))
      (node (ref "U6") (pin "4") (pinfunction "FAULT_4") (pintype "bidirectional"))
    )
    (net (code "18") (name "LED_VCC") (class "Default")
      (node (ref "C18") (pin "2") (pinfunction "2_2") (pintype "passive"))
      (node (ref "C19") (pin "2") (pinfunction "2_2") (pintype "passive"))
      (node (ref "C20") (pin "2") (pinfunction "2_2") (pintype "passive"))
      (node (ref "C21") (pin "2") (pinfunction "2_2") (pintype "passive"))
      (node (ref "C22") (pin "2") (pinfunction "2_2") (pintype "passive"))
      (node (ref "C23") (pin "2") (pinfunction "2_2") (pintype "passive"))
      (node (ref "C24") (pin "2") (pinfunction "2_2") (pintype "passive"))
      (node (ref "C25") (pin "2") (pinfunction "2_2") (pintype "passive"))
      (node (ref "C26") (pin "2") (pinfunction "2_2") (pintype "passive"))
      (node (ref "C27") (pin "2") (pinfunction "2_2") (pintype "passive"))
      (node (ref "C28") (pin "2") (pinfunction "2_2") (pintype "passive"))
      (node (ref "C29") (pin "2") (pinfunction "2_2") (pintype "passive"))
      (node (ref "C30") (pin "2") (pinfunction "2_2") (pintype "passive"))
      (node (ref "C31") (pin "2") (pinfunction "2_2") (pintype "passive"))
      (node (ref "C32") (pin "2") (pinfunction "2_2") (pintype "passive"))
      (node (ref "C33") (pin "2") (pinfunction "2_2") (pintype "passive"))
      (node (ref "C34") (pin "2") (pinfunction "2_2") (pintype "passive"))
      (node (ref "C35") (pin "2") (pinfunction "2_2") (pintype "passive"))
      (node (ref "C36") (pin "2") (pinfunction "2_2") (pintype "passive"))
      (node (ref "C37") (pin "2") (pinfunction "2_2") (pintype "passive"))
      (node (ref "C38") (pin "2") (pinfunction "2_2") (pintype "passive"))
      (node (ref "C39") (pin "2") (pinfunction "2_2") (pintype "passive"))
      (node (ref "C40") (pin "2") (pinfunction "2_2") (pintype "passive"))
      (node (ref "C41") (pin "2") (pinfunction "2_2") (pintype "passive"))
      (node (ref "C42") (pin "2") (pinfunction "2_2") (pintype "passive"))
      (node (ref "C43") (pin "2") (pinfunction "2_2") (pintype "passive"))
      (node (ref "C44") (pin "2") (pinfunction "2_2") (pintype "passive"))
      (node (ref "C45") (pin "2") (pinfunction "2_2") (pintype "passive"))
      (node (ref "C46") (pin "2") (pinfunction "2_2") (pintype "passive"))
      (node (ref "C47") (pin "2") (pinfunction "2_2") (pintype "passive"))
      (node (ref "C48") (pin "2") (pinfunction "2_2") (pintype "passive"))
      (node (ref "C49") (pin "2") (pinfunction "2_2") (pintype "passive"))
      (node (ref "C50") (pin "2") (pinfunction "2_2") (pintype "passive"))
      (node (ref "C51") (pin "2") (pinfunction "2_2") (pintype "passive"))
      (node (ref "C52") (pin "2") (pinfunction "2_2") (pintype "passive"))
      (node (ref "LED1") (pin "VDD") (pinfunction "VDD_VDD") (pintype "power_in"))
      (node (ref "LED10") (pin "VDD") (pinfunction "VDD_VDD") (pintype "power_in"))
      (node (ref "LED11") (pin "VDD") (pinfunction "VDD_VDD") (pintype "power_in"))
      (node (ref "LED12") (pin "VDD") (pinfunction "VDD_VDD") (pintype "power_in"))
      (node (ref "LED13") (pin "VDD") (pinfunction "VDD_VDD") (pintype "power_in"))
      (node (ref "LED14") (pin "VDD") (pinfunction "VDD_VDD") (pintype "power_in"))
      (node (ref "LED15") (pin "VDD") (pinfunction "VDD_VDD") (pintype "power_in"))
      (node (ref "LED16") (pin "VDD") (pinfunction "VDD_VDD") (pintype "power_in"))
      (node (ref "LED17") (pin "VDD") (pinfunction "VDD_VDD") (pintype "power_in"))
      (node (ref "LED18") (pin "VDD") (pinfunction "VDD_VDD") (pintype "power_in"))
      (node (ref "LED19") (pin "VDD") (pinfunction "VDD_VDD") (pintype "power_in"))
      (node (ref "LED2") (pin "VDD") (pinfunction "VDD_VDD") (pintype "power_in"))
      (node (ref "LED20") (pin "VDD") (pinfunction "VDD_VDD") (pintype "power_in"))
      (node (ref "LED21") (pin "VDD") (pinfunction "VDD_VDD") (pintype "power_in"))
      (node (ref "LED22") (pin "VDD") (pinfunction "VDD_VDD") (pintype "power_in"))
      (node (ref "LED23") (pin "VDD") (pinfunction "VDD_VDD") (pintype "power_in"))
      (node (ref "LED24") (pin "VDD") (pinfunction "VDD_VDD") (pintype "power_in"))
      (node (ref "LED25") (pin "VDD") (pinfunction "VDD_VDD") (pintype "power_in"))
      (node (ref "LED26") (pin "VDD") (pinfunction "VDD_VDD") (pintype "power_in"))
      (node (ref "LED27") (pin "VDD") (pinfunction "VDD_VDD") (pintype "power_in"))
      (node (ref "LED28") (pin "VDD") (pinfunction "VDD_VDD") (pintype "power_in"))
      (node (ref "LED29") (pin "VDD") (pinfunction "VDD_VDD") (pintype "power_in"))
      (node (ref "LED3") (pin "VDD") (pinfunction "VDD_VDD") (pintype "power_in"))
      (node (ref "LED30") (pin "VDD") (pinfunction "VDD_VDD") (pintype "power_in"))
      (node (ref "LED31") (pin "VDD") (pinfunction "VDD_VDD") (pintype "power_in"))
      (node (ref "LED32") (pin "VDD") (pinfunction "VDD_VDD") (pintype "power_in"))
      (node (ref "LED33") (pin "VDD") (pinfunction "VDD_VDD") (pintype "power_in"))
      (node (ref "LED34") (pin "VDD") (pinfunction "VDD_VDD") (pintype "power_in"))
      (node (ref "LED35") (pin "VDD") (pinfunction "VDD_VDD") (pintype "power_in"))
      (node (ref "LED36") (pin "VDD") (pinfunction "VDD_VDD") (pintype "power_in"))
      (node (ref "LED37") (pin "VDD") (pinfunction "VDD_VDD") (pintype "power_in"))
      (node (ref "LED38") (pin "VDD") (pinfunction "VDD_VDD") (pintype "power_in"))
      (node (ref "LED39") (pin "VDD") (pinfunction "VDD_VDD") (pintype "power_in"))
      (node (ref "LED4") (pin "VDD") (pinfunction "VDD_VDD") (pintype "power_in"))
      (node (ref "LED40") (pin "VDD") (pinfunction "VDD_VDD") (pintype "power_in"))
      (node (ref "LED41") (pin "VDD") (pinfunction "VDD_VDD") (pintype "power_in"))
      (node (ref "LED5") (pin "VDD") (pinfunction "VDD_VDD") (pintype "power_in"))
      (node (ref "LED6") (pin "VDD") (pinfunction "VDD_VDD") (pintype "power_in"))
      (node (ref "LED7") (pin "VDD") (pinfunction "VDD_VDD") (pintype "power_in"))
      (node (ref "LED8") (pin "VDD") (pinfunction "VDD_VDD") (pintype "power_in"))
      (node (ref "LED9") (pin "VDD") (pinfunction "VDD_VDD") (pintype "power_in"))
      (node (ref "U6") (pin "6") (pinfunction "OUT_6") (pintype "bidirectional"))
    )
    (net (code "19") (name "NRST") (class "Default")
      (node (ref "C9") (pin "1") (pinfunction "1_1") (pintype "passive"))
      (node (ref "PH1") (pin "2") (pinfunction "2_2") (pintype "passive"))
      (node (ref "Q1") (pin "3") (pinfunction "C_3") (pintype "bidirectional"))
      (node (ref "U3") (pin "7") (pinfunction "NRST_7") (pintype "bidirectional"))
    )
    (net (code "20") (name "Net-(C16-Pad1)") (class "Default")
      (node (ref "C16") (pin "1") (pinfunction "1_1") (pintype "passive"))
      (node (ref "D3") (pin "C") (pinfunction "C_C") (pintype "passive"))
      (node (ref "R9") (pin "1") (pinfunction "1_1") (pintype "passive"))
    )
    (net (code "21") (name "Net-(D4-PadA)") (class "Default")
      (node (ref "D4") (pin "A") (pinfunction "A_A") (pintype "passive"))
      (node (ref "SW2") (pin "HOLE2") (pinfunction "P0_HOLE2") (pintype "bidirectional"))
      (node (ref "SW2") (pin "P$2") (pinfunction "P0_P$2") (pintype "bidirectional"))
    )
    (net (code "22") (name "Net-(D5-PadA)") (class "Default")
      (node (ref "D5") (pin "A") (pinfunction "A_A") (pintype "passive"))
      (node (ref "SW3") (pin "HOLE2") (pinfunction "P0_HOLE2") (pintype "bidirectional"))
      (node (ref "SW3") (pin "P$2") (pinfunction "P0_P$2") (pintype "bidirectional"))
    )
    (net (code "23") (name "Net-(D6-PadA)") (class "Default")
      (node (ref "D6") (pin "A") (pinfunction "A_A") (pintype "passive"))
      (node (ref "SW4") (pin "HOLE2") (pinfunction "P0_HOLE2") (pintype "bidirectional"))
      (node (ref "SW4") (pin "P$2") (pinfunction "P0_P$2") (pintype "bidirectional"))
    )
    (net (code "24") (name "Net-(D7-PadA)") (class "Default")
      (node (ref "D7") (pin "A") (pinfunction "A_A") (pintype "passive"))
      (node (ref "SW5") (pin "HOLE2") (pinfunction "P0_HOLE2") (pintype "bidirectional"))
      (node (ref "SW5") (pin "P$2") (pinfunction "P0_P$2") (pintype "bidirectional"))
    )
    (net (code "25") (name "Net-(D8-PadA)") (class "Default")
      (node (ref "D8") (pin "A") (pinfunction "A_A") (pintype "passive"))
      (node (ref "SW6") (pin "HOLE2") (pinfunction "P0_HOLE2") (pintype "bidirectional"))
      (node (ref "SW6") (pin "P$2") (pinfunction "P0_P$2") (pintype "bidirectional"))
    )
    (net (code "26") (name "Net-(D9-PadA)") (class "Default")
      (node (ref "D9") (pin "A") (pinfunction "A_A") (pintype "passive"))
      (node (ref "SW7") (pin "HOLE2") (pinfunction "P0_HOLE2") (pintype "bidirectional"))
      (node (ref "SW7") (pin "P$2") (pinfunction "P0_P$2") (pintype "bidirectional"))
    )
    (net (code "27") (name "Net-(D10-PadA)") (class "Default")
      (node (ref "D10") (pin "A") (pinfunction "A_A") (pintype "passive"))
      (node (ref "SW8") (pin "HOLE2") (pinfunction "P0_HOLE2") (pintype "bidirectional"))
      (node (ref "SW8") (pin "P$2") (pinfunction "P0_P$2") (pintype "bidirectional"))
    )
    (net (code "28") (name "Net-(D11-PadA)") (class "Default")
      (node (ref "D11") (pin "A") (pinfunction "A_A") (pintype "passive"))
      (node (ref "SW9") (pin "HOLE2") (pinfunction "P0_HOLE2") (pintype "bidirectional"))
      (node (ref "SW9") (pin "P$2") (pinfunction "P0_P$2") (pintype "bidirectional"))
    )
    (net (code "29") (name "Net-(D12-PadA)") (class "Default")
      (node (ref "D12") (pin "A") (pinfunction "A_A") (pintype "passive"))
      (node (ref "SW10") (pin "HOLE2") (pinfunction "P0_HOLE2") (pintype "bidirectional"))
      (node (ref "SW10") (pin "P$2") (pinfunction "P0_P$2") (pintype "bidirectional"))
    )
    (net (code "30") (name "Net-(D13-PadA)") (class "Default")
      (node (ref "D13") (pin "A") (pinfunction "A_A") (pintype "passive"))
      (node (ref "SW11") (pin "HOLE2") (pinfunction "P0_HOLE2") (pintype "bidirectional"))
      (node (ref "SW11") (pin "P$2") (pinfunction "P0_P$2") (pintype "bidirectional"))
    )
    (net (code "31") (name "Net-(D14-PadA)") (class "Default")
      (node (ref "D14") (pin "A") (pinfunction "A_A") (pintype "passive"))
      (node (ref "SW12") (pin "HOLE2") (pinfunction "P0_HOLE2") (pintype "bidirectional"))
      (node (ref "SW12") (pin "P$2") (pinfunction "P0_P$2") (pintype "bidirectional"))
    )
    (net (code "32") (name "Net-(D15-PadA)") (class "Default")
      (node (ref "D15") (pin "A") (pinfunction "A_A") (pintype "passive"))
      (node (ref "SW13") (pin "HOLE2") (pinfunction "P0_HOLE2") (pintype "bidirectional"))
      (node (ref "SW13") (pin "P$2") (pinfunction "P0_P$2") (pintype "bidirectional"))
    )
    (net (code "33") (name "Net-(D16-PadA)") (class "Default")
      (node (ref "D16") (pin "A") (pinfunction "A_A") (pintype "passive"))
      (node (ref "SW14") (pin "HOLE2") (pinfunction "P0_HOLE2") (pintype "bidirectional"))
      (node (ref "SW14") (pin "P$2") (pinfunction "P0_P$2") (pintype "bidirectional"))
    )
    (net (code "34") (name "Net-(D17-PadA)") (class "Default")
      (node (ref "D17") (pin "A") (pinfunction "A_A") (pintype "passive"))
      (node (ref "SW15") (pin "HOLE2") (pinfunction "P0_HOLE2") (pintype "bidirectional"))
      (node (ref "SW15") (pin "P$2") (pinfunction "P0_P$2") (pintype "bidirectional"))
    )
    (net (code "35") (name "Net-(D18-PadA)") (class "Default")
      (node (ref "D18") (pin "A") (pinfunction "A_A") (pintype "passive"))
      (node (ref "SW16") (pin "HOLE2") (pinfunction "P0_HOLE2") (pintype "bidirectional"))
      (node (ref "SW16") (pin "P$2") (pinfunction "P0_P$2") (pintype "bidirectional"))
    )
    (net (code "36") (name "Net-(D19-PadA)") (class "Default")
      (node (ref "D19") (pin "A") (pinfunction "A_A") (pintype "passive"))
      (node (ref "SW17") (pin "HOLE2") (pinfunction "P0_HOLE2") (pintype "bidirectional"))
      (node (ref "SW17") (pin "P$2") (pinfunction "P0_P$2") (pintype "bidirectional"))
    )
    (net (code "37") (name "Net-(D20-PadA)") (class "Default")
      (node (ref "D20") (pin "A") (pinfunction "A_A") (pintype "passive"))
      (node (ref "SW18") (pin "HOLE2") (pinfunction "P0_HOLE2") (pintype "bidirectional"))
      (node (ref "SW18") (pin "P$2") (pinfunction "P0_P$2") (pintype "bidirectional"))
    )
    (net (code "38") (name "Net-(D21-PadA)") (class "Default")
      (node (ref "D21") (pin "A") (pinfunction "A_A") (pintype "passive"))
      (node (ref "SW19") (pin "HOLE2") (pinfunction "P0_HOLE2") (pintype "bidirectional"))
      (node (ref "SW19") (pin "P$2") (pinfunction "P0_P$2") (pintype "bidirectional"))
    )
    (net (code "39") (name "Net-(D22-PadA)") (class "Default")
      (node (ref "D22") (pin "A") (pinfunction "A_A") (pintype "passive"))
      (node (ref "SW20") (pin "HOLE2") (pinfunction "P0_HOLE2") (pintype "bidirectional"))
      (node (ref "SW20") (pin "P$2") (pinfunction "P0_P$2") (pintype "bidirectional"))
    )
    (net (code "40") (name "Net-(D23-PadA)") (class "Default")
      (node (ref "D23") (pin "A") (pinfunction "A_A") (pintype "passive"))
      (node (ref "SW21") (pin "HOLE2") (pinfunction "P0_HOLE2") (pintype "bidirectional"))
      (node (ref "SW21") (pin "P$2") (pinfunction "P0_P$2") (pintype "bidirectional"))
    )
    (net (code "41") (name "Net-(D24-PadA)") (class "Default")
      (node (ref "D24") (pin "A") (pinfunction "A_A") (pintype "passive"))
      (node (ref "SW22") (pin "HOLE2") (pinfunction "P0_HOLE2") (pintype "bidirectional"))
      (node (ref "SW22") (pin "P$2") (pinfunction "P0_P$2") (pintype "bidirectional"))
    )
    (net (code "42") (name "Net-(D25-PadA)") (class "Default")
      (node (ref "D25") (pin "A") (pinfunction "A_A") (pintype "passive"))
      (node (ref "SW23") (pin "HOLE2") (pinfunction "P0_HOLE2") (pintype "bidirectional"))
      (node (ref "SW23") (pin "P$2") (pinfunction "P0_P$2") (pintype "bidirectional"))
    )
    (net (code "43") (name "Net-(D26-PadA)") (class "Default")
      (node (ref "D26") (pin "A") (pinfunction "A_A") (pintype "passive"))
      (node (ref "SW24") (pin "HOLE2") (pinfunction "P0_HOLE2") (pintype "bidirectional"))
      (node (ref "SW24") (pin "P$2") (pinfunction "P0_P$2") (pintype "bidirectional"))
    )
    (net (code "44") (name "Net-(D27-PadA)") (class "Default")
      (node (ref "D27") (pin "A") (pinfunction "A_A") (pintype "passive"))
      (node (ref "SW25") (pin "HOLE2") (pinfunction "P0_HOLE2") (pintype "bidirectional"))
      (node (ref "SW25") (pin "P$2") (pinfunction "P0_P$2") (pintype "bidirectional"))
    )
    (net (code "45") (name "Net-(D28-PadA)") (class "Default")
      (node (ref "D28") (pin "A") (pinfunction "A_A") (pintype "passive"))
      (node (ref "SW26") (pin "HOLE2") (pinfunction "P0_HOLE2") (pintype "bidirectional"))
      (node (ref "SW26") (pin "P$2") (pinfunction "P0_P$2") (pintype "bidirectional"))
    )
    (net (code "46") (name "Net-(D29-PadA)") (class "Default")
      (node (ref "D29") (pin "A") (pinfunction "A_A") (pintype "passive"))
      (node (ref "SW27") (pin "HOLE2") (pinfunction "P0_HOLE2") (pintype "bidirectional"))
      (node (ref "SW27") (pin "P$2") (pinfunction "P0_P$2") (pintype "bidirectional"))
    )
    (net (code "47") (name "Net-(D30-PadA)") (class "Default")
      (node (ref "D30") (pin "A") (pinfunction "A_A") (pintype "passive"))
      (node (ref "SW28") (pin "HOLE2") (pinfunction "P0_HOLE2") (pintype "bidirectional"))
      (node (ref "SW28") (pin "P$2") (pinfunction "P0_P$2") (pintype "bidirectional"))
    )
    (net (code "48") (name "Net-(D31-PadA)") (class "Default")
      (node (ref "D31") (pin "A") (pinfunction "A_A") (pintype "passive"))
      (node (ref "SW29") (pin "HOLE2") (pinfunction "P0_HOLE2") (pintype "bidirectional"))
      (node (ref "SW29") (pin "P$2") (pinfunction "P0_P$2") (pintype "bidirectional"))
    )
    (net (code "49") (name "Net-(D32-PadA)") (class "Default")
      (node (ref "D32") (pin "A") (pinfunction "A_A") (pintype "passive"))
      (node (ref "SW30") (pin "HOLE2") (pinfunction "P0_HOLE2") (pintype "bidirectional"))
      (node (ref "SW30") (pin "P$2") (pinfunction "P0_P$2") (pintype "bidirectional"))
    )
    (net (code "50") (name "Net-(D33-PadA)") (class "Default")
      (node (ref "D33") (pin "A") (pinfunction "A_A") (pintype "passive"))
      (node (ref "SW31") (pin "HOLE2") (pinfunction "P0_HOLE2") (pintype "bidirectional"))
      (node (ref "SW31") (pin "P$2") (pinfunction "P0_P$2") (pintype "bidirectional"))
    )
    (net (code "51") (name "Net-(D34-PadA)") (class "Default")
      (node (ref "D34") (pin "A") (pinfunction "A_A") (pintype "passive"))
      (node (ref "SW32") (pin "HOLE2") (pinfunction "P0_HOLE2") (pintype "bidirectional"))
      (node (ref "SW32") (pin "P$2") (pinfunction "P0_P$2") (pintype "bidirectional"))
    )
    (net (code "52") (name "Net-(D35-PadA)") (class "Default")
      (node (ref "D35") (pin "A") (pinfunction "A_A") (pintype "passive"))
      (node (ref "SW33") (pin "HOLE2") (pinfunction "P0_HOLE2") (pintype "bidirectional"))
      (node (ref "SW33") (pin "P$2") (pinfunction "P0_P$2") (pintype "bidirectional"))
    )
    (net (code "53") (name "Net-(D36-PadA)") (class "Default")
      (node (ref "D36") (pin "A") (pinfunction "A_A") (pintype "passive"))
      (node (ref "SW34") (pin "HOLE2") (pinfunction "P0_HOLE2") (pintype "bidirectional"))
      (node (ref "SW34") (pin "P$2") (pinfunction "P0_P$2") (pintype "bidirectional"))
    )
    (net (code "54") (name "Net-(D37-PadA)") (class "Default")
      (node (ref "D37") (pin "A") (pinfunction "A_A") (pintype "passive"))
      (node (ref "SW35") (pin "HOLE2") (pinfunction "P0_HOLE2") (pintype "bidirectional"))
      (node (ref "SW35") (pin "P$2") (pinfunction "P0_P$2") (pintype "bidirectional"))
    )
    (net (code "55") (name "Net-(D38-PadA)") (class "Default")
      (node (ref "D38") (pin "A") (pinfunction "A_A") (pintype "passive"))
      (node (ref "SW36") (pin "HOLE2") (pinfunction "P0_HOLE2") (pintype "bidirectional"))
      (node (ref "SW36") (pin "P$2") (pinfunction "P0_P$2") (pintype "bidirectional"))
    )
    (net (code "56") (name "Net-(D39-PadA)") (class "Default")
      (node (ref "D39") (pin "A") (pinfunction "A_A") (pintype "passive"))
      (node (ref "SW37") (pin "HOLE2") (pinfunction "P0_HOLE2") (pintype "bidirectional"))
      (node (ref "SW37") (pin "P$2") (pinfunction "P0_P$2") (pintype "bidirectional"))
    )
    (net (code "57") (name "Net-(D40-PadA)") (class "Default")
      (node (ref "D40") (pin "A") (pinfunction "A_A") (pintype "passive"))
      (node (ref "SW38") (pin "HOLE2") (pinfunction "P0_HOLE2") (pintype "bidirectional"))
      (node (ref "SW38") (pin "P$2") (pinfunction "P0_P$2") (pintype "bidirectional"))
    )
    (net (code "58") (name "Net-(D41-PadA)") (class "Default")
      (node (ref "D41") (pin "A") (pinfunction "A_A") (pintype "passive"))
      (node (ref "SW39") (pin "HOLE2") (pinfunction "P0_HOLE2") (pintype "bidirectional"))
      (node (ref "SW39") (pin "P$2") (pinfunction "P0_P$2") (pintype "bidirectional"))
    )
    (net (code "59") (name "Net-(D42-PadA)") (class "Default")
      (node (ref "D42") (pin "A") (pinfunction "A_A") (pintype "passive"))
      (node (ref "SW40") (pin "HOLE2") (pinfunction "P0_HOLE2") (pintype "bidirectional"))
      (node (ref "SW40") (pin "P$2") (pinfunction "P0_P$2") (pintype "bidirectional"))
    )
    (net (code "60") (name "Net-(D43-PadA)") (class "Default")
      (node (ref "D43") (pin "A") (pinfunction "A_A") (pintype "passive"))
      (node (ref "SW41") (pin "HOLE2") (pinfunction "P0_HOLE2") (pintype "bidirectional"))
      (node (ref "SW41") (pin "P$2") (pinfunction "P0_P$2") (pintype "bidirectional"))
    )
    (net (code "61") (name "Net-(D44-PadA)") (class "Default")
      (node (ref "D44") (pin "A") (pinfunction "A_A") (pintype "passive"))
      (node (ref "SW42") (pin "HOLE2") (pinfunction "P0_HOLE2") (pintype "bidirectional"))
      (node (ref "SW42") (pin "P$2") (pinfunction "P0_P$2") (pintype "bidirectional"))
    )
    (net (code "62") (name "Net-(LED1-DI)") (class "Default")
      (node (ref "LED1") (pin "DIN") (pinfunction "DI_DIN") (pintype "input"))
      (node (ref "LED2") (pin "DOUT") (pinfunction "DO_DOUT") (pintype "output"))
    )
    (net (code "63") (name "Net-(LED2-DI)") (class "Default")
      (node (ref "LED2") (pin "DIN") (pinfunction "DI_DIN") (pintype "input"))
      (node (ref "LED3") (pin "DOUT") (pinfunction "DO_DOUT") (pintype "output"))
    )
    (net (code "64") (name "Net-(LED3-DI)") (class "Default")
      (node (ref "LED3") (pin "DIN") (pinfunction "DI_DIN") (pintype "input"))
      (node (ref "LED4") (pin "DOUT") (pinfunction "DO_DOUT") (pintype "output"))
    )
    (net (code "65") (name "Net-(LED4-DI)") (class "Default")
      (node (ref "LED4") (pin "DIN") (pinfunction "DI_DIN") (pintype "input"))
      (node (ref "LED5") (pin "DOUT") (pinfunction "DO_DOUT") (pintype "output"))
    )
    (net (code "66") (name "Net-(LED5-DI)") (class "Default")
      (node (ref "LED5") (pin "DIN") (pinfunction "DI_DIN") (pintype "input"))
      (node (ref "LED6") (pin "DOUT") (pinfunction "DO_DOUT") (pintype "output"))
    )
    (net (code "67") (name "Net-(LED6-DI)") (class "Default")
      (node (ref "LED6") (pin "DIN") (pinfunction "DI_DIN") (pintype "input"))
      (node (ref "LED7") (pin "DOUT") (pinfunction "DO_DOUT") (pintype "output"))
    )
    (net (code "68") (name "Net-(LED7-DI)") (class "Default")
      (node (ref "LED7") (pin "DIN") (pinfunction "DI_DIN") (pintype "input"))
      (node (ref "LED8") (pin "DOUT") (pinfunction "DO_DOUT") (pintype "output"))
    )
    (net (code "69") (name "Net-(LED8-DI)") (class "Default")
      (node (ref "LED8") (pin "DIN") (pinfunction "DI_DIN") (pintype "input"))
      (node (ref "LED9") (pin "DOUT") (pinfunction "DO_DOUT") (pintype "output"))
    )
    (net (code "70") (name "Net-(LED10-DI)") (class "Default")
      (node (ref "LED10") (pin "DIN") (pinfunction "DI_DIN") (pintype "input"))
      (node (ref "LED11") (pin "DOUT") (pinfunction "DO_DOUT") (pintype "output"))
    )
    (net (code "71") (name "Net-(LED10-DO)") (class "Default")
      (node (ref "LED10") (pin "DOUT") (pinfunction "DO_DOUT") (pintype "output"))
      (node (ref "LED9") (pin "DIN") (pinfunction "DI_DIN") (pintype "input"))
    )
    (net (code "72") (name "Net-(LED11-DI)") (class "Default")
      (node (ref "LED11") (pin "DIN") (pinfunction "DI_DIN") (pintype "input"))
      (node (ref "LED12") (pin "DOUT") (pinfunction "DO_DOUT") (pintype "output"))
    )
    (net (code "73") (name "Net-(LED12-DI)") (class "Default")
      (node (ref "LED12") (pin "DIN") (pinfunction "DI_DIN") (pintype "input"))
      (node (ref "LED13") (pin "DOUT") (pinfunction "DO_DOUT") (pintype "output"))
    )
    (net (code "74") (name "Net-(LED13-DI)") (class "Default")
      (node (ref "LED13") (pin "DIN") (pinfunction "DI_DIN") (pintype "input"))
      (node (ref "LED14") (pin "DOUT") (pinfunction "DO_DOUT") (pintype "output"))
    )
    (net (code "75") (name "Net-(LED14-DI)") (class "Default")
      (node (ref "LED14") (pin "DIN") (pinfunction "DI_DIN") (pintype "input"))
      (node (ref "LED15") (pin "DOUT") (pinfunction "DO_DOUT") (pintype "output"))
    )
    (net (code "76") (name "Net-(LED15-DI)") (class "Default")
      (node (ref "LED15") (pin "DIN") (pinfunction "DI_DIN") (pintype "input"))
      (node (ref "LED16") (pin "DOUT") (pinfunction "DO_DOUT") (pintype "output"))
    )
    (net (code "77") (name "Net-(LED16-DI)") (class "Default")
      (node (ref "LED16") (pin "DIN") (pinfunction "DI_DIN") (pintype "input"))
      (node (ref "LED17") (pin "DOUT") (pinfunction "DO_DOUT") (pintype "output"))
    )
    (net (code "78") (name "Net-(LED17-DI)") (class "Default")
      (node (ref "LED17") (pin "DIN") (pinfunction "DI_DIN") (pintype "input"))
      (node (ref "LED18") (pin "DOUT") (pinfunction "DO_DOUT") (pintype "output"))
    )
    (net (code "79") (name "Net-(LED18-DI)") (class "Default")
      (node (ref "LED18") (pin "DIN") (pinfunction "DI_DIN") (pintype "input"))
      (node (ref "LED19") (pin "DOUT") (pinfunction "DO_DOUT") (pintype "output"))
    )
    (net (code "80") (name "Net-(LED19-DI)") (class "Default")
      (node (ref "LED19") (pin "DIN") (pinfunction "DI_DIN") (pintype "input"))
      (node (ref "LED20") (pin "DOUT") (pinfunction "DO_DOUT") (pintype "output"))
    )
    (net (code "81") (name "Net-(LED20-DI)") (class "Default")
      (node (ref "LED20") (pin "DIN") (pinfunction "DI_DIN") (pintype "input"))
      (node (ref "LED21") (pin "DOUT") (pinfunction "DO_DOUT") (pintype "output"))
    )
    (net (code "82") (name "Net-(LED21-DI)") (class "Default")
      (node (ref "LED21") (pin "DIN") (pinfunction "DI_DIN") (pintype "input"))
      (node (ref "LED22") (pin "DOUT") (pinfunction "DO_DOUT") (pintype "output"))
    )
    (net (code "83") (name "Net-(LED22-DI)") (class "Default")
      (node (ref "LED22") (pin "DIN") (pinfunction "DI_DIN") (pintype "input"))
      (node (ref "LED23") (pin "DOUT") (pinfunction "DO_DOUT") (pintype "output"))
    )
    (net (code "84") (name "Net-(LED23-DI)") (class "Default")
      (node (ref "LED23") (pin "DIN") (pinfunction "DI_DIN") (pintype "input"))
      (node (ref "LED24") (pin "DOUT") (pinfunction "DO_DOUT") (pintype "output"))
    )
    (net (code "85") (name "Net-(LED24-DI)") (class "Default")
      (node (ref "LED24") (pin "DIN") (pinfunction "DI_DIN") (pintype "input"))
      (node (ref "LED25") (pin "DOUT") (pinfunction "DO_DOUT") (pintype "output"))
    )
    (net (code "86") (name "Net-(LED25-DI)") (class "Default")
      (node (ref "LED25") (pin "DIN") (pinfunction "DI_DIN") (pintype "input"))
      (node (ref "LED26") (pin "DOUT") (pinfunction "DO_DOUT") (pintype "output"))
    )
    (net (code "87") (name "Net-(LED26-DI)") (class "Default")
      (node (ref "LED26") (pin "DIN") (pinfunction "DI_DIN") (pintype "input"))
      (node (ref "LED27") (pin "DOUT") (pinfunction "DO_DOUT") (pintype "output"))
    )
    (net (code "88") (name "Net-(LED27-DI)") (class "Default")
      (node (ref "LED27") (pin "DIN") (pinfunction "DI_DIN") (pintype "input"))
      (node (ref "LED28") (pin "DOUT") (pinfunction "DO_DOUT") (pintype "output"))
    )
    (net (code "89") (name "Net-(LED28-DI)") (class "Default")
      (node (ref "LED28") (pin "DIN") (pinfunction "DI_DIN") (pintype "input"))
      (node (ref "LED29") (pin "DOUT") (pinfunction "DO_DOUT") (pintype "output"))
    )
    (net (code "90") (name "Net-(LED29-DI)") (class "Default")
      (node (ref "LED29") (pin "DIN") (pinfunction "DI_DIN") (pintype "input"))
      (node (ref "LED30") (pin "DOUT") (pinfunction "DO_DOUT") (pintype "output"))
    )
    (net (code "91") (name "Net-(LED30-DI)") (class "Default")
      (node (ref "LED30") (pin "DIN") (pinfunction "DI_DIN") (pintype "input"))
      (node (ref "LED31") (pin "DOUT") (pinfunction "DO_DOUT") (pintype "output"))
    )
    (net (code "92") (name "Net-(LED31-DI)") (class "Default")
      (node (ref "LED31") (pin "DIN") (pinfunction "DI_DIN") (pintype "input"))
      (node (ref "LED32") (pin "DOUT") (pinfunction "DO_DOUT") (pintype "output"))
    )
    (net (code "93") (name "Net-(LED32-DI)") (class "Default")
      (node (ref "LED32") (pin "DIN") (pinfunction "DI_DIN") (pintype "input"))
      (node (ref "LED33") (pin "DOUT") (pinfunction "DO_DOUT") (pintype "output"))
    )
    (net (code "94") (name "Net-(LED33-DI)") (class "Default")
      (node (ref "LED33") (pin "DIN") (pinfunction "DI_DIN") (pintype "input"))
      (node (ref "LED34") (pin "DOUT") (pinfunction "DO_DOUT") (pintype "output"))
    )
    (net (code "95") (name "Net-(LED34-DI)") (class "Default")
      (node (ref "LED34") (pin "DIN") (pinfunction "DI_DIN") (pintype "input"))
      (node (ref "LED35") (pin "DOUT") (pinfunction "DO_DOUT") (pintype "output"))
    )
    (net (code "96") (name "Net-(LED35-DI)") (class "Default")
      (node (ref "LED35") (pin "DIN") (pinfunction "DI_DIN") (pintype "input"))
      (node (ref "LED36") (pin "DOUT") (pinfunction "DO_DOUT") (pintype "output"))
    )
    (net (code "97") (name "Net-(LED36-DI)") (class "Default")
      (node (ref "LED36") (pin "DIN") (pinfunction "DI_DIN") (pintype "input"))
      (node (ref "LED37") (pin "DOUT") (pinfunction "DO_DOUT") (pintype "output"))
    )
    (net (code "98") (name "Net-(LED37-DI)") (class "Default")
      (node (ref "LED37") (pin "DIN") (pinfunction "DI_DIN") (pintype "input"))
      (node (ref "LED38") (pin "DOUT") (pinfunction "DO_DOUT") (pintype "output"))
    )
    (net (code "99") (name "Net-(LED38-DI)") (class "Default")
      (node (ref "LED38") (pin "DIN") (pinfunction "DI_DIN") (pintype "input"))
      (node (ref "LED39") (pin "DOUT") (pinfunction "DO_DOUT") (pintype "output"))
    )
    (net (code "100") (name "Net-(LED39-DI)") (class "Default")
      (node (ref "LED39") (pin "DIN") (pinfunction "DI_DIN") (pintype "input"))
      (node (ref "LED40") (pin "DOUT") (pinfunction "DO_DOUT") (pintype "output"))
    )
    (net (code "101") (name "Net-(LED40-DI)") (class "Default")
      (node (ref "LED40") (pin "DIN") (pinfunction "DI_DIN") (pintype "input"))
      (node (ref "LED41") (pin "DOUT") (pinfunction "DO_DOUT") (pintype "output"))
    )
    (net (code "102") (name "Net-(Q1-B)") (class "Default")
      (node (ref "D2") (pin "A") (pinfunction "A_A") (pintype "passive"))
      (node (ref "Q1") (pin "1") (pinfunction "B_1") (pintype "bidirectional"))
      (node (ref "SW1") (pin "P$1") (pinfunction "P$1_P$1") (pintype "bidirectional"))
    )
    (net (code "103") (name "Net-(R1-Pad1)") (class "Default")
      (node (ref "R1") (pin "1") (pinfunction "1_1") (pintype "passive"))
      (node (ref "X1") (pin "CC1") (pinfunction "CC1_CC1") (pintype "passive"))
    )
    (net (code "104") (name "Net-(R3-Pad1)") (class "Default")
      (node (ref "R3") (pin "1") (pinfunction "1_1") (pintype "passive"))
      (node (ref "X1") (pin "CC2") (pinfunction "CC2_CC2") (pintype "input"))
    )
    (net (code "105") (name "Net-(U5-VIN-)") (class "Default")
      (node (ref "R10") (pin "2") (pinfunction "2_2") (pintype "passive"))
      (node (ref "SJ1") (pin "2") (pinfunction "2_2") (pintype "passive"))
      (node (ref "U5") (pin "2") (pinfunction "VIN-_2") (pintype "bidirectional"))
      (node (ref "U6") (pin "1") (pinfunction "IN_1") (pintype "bidirectional"))
    )
    (net (code "106") (name "Net-(U6-ILIM)") (class "Default")
      (node (ref "R11") (pin "2") (pinfunction "2_2") (pintype "passive"))
      (node (ref "U6") (pin "5") (pinfunction "ILIM_5") (pintype "bidirectional"))
    )
    (net (code "107") (name "ROW0") (class "Default")
      (node (ref "D10") (pin "C") (pinfunction "C_C") (pintype "passive"))
      (node (ref "D11") (pin "C") (pinfunction "C_C") (pintype "passive"))
      (node (ref "D4") (pin "C") (pinfunction "C_C") (pintype "passive"))
      (node (ref "D5") (pin "C") (pinfunction "C_C") (pintype "passive"))
      (node (ref "D6") (pin "C") (pinfunction "C_C") (pintype "passive"))
      (node (ref "D7") (pin "C") (pinfunction "C_C") (pintype "passive"))
      (node (ref "D8") (pin "C") (pinfunction "C_C") (pintype "passive"))
      (node (ref "D9") (pin "C") (pinfunction "C_C") (pintype "passive"))
      (node (ref "U3") (pin "29") (pinfunction "PA8_29") (pintype "bidirectional"))
    )
    (net (code "108") (name "ROW1") (class "Default")
      (node (ref "D12") (pin "C") (pinfunction "C_C") (pintype "passive"))
      (node (ref "D13") (pin "C") (pinfunction "C_C") (pintype "passive"))
      (node (ref "D14") (pin "C") (pinfunction "C_C") (pintype "passive"))
      (node (ref "D15") (pin "C") (pinfunction "C_C") (pintype "passive"))
      (node (ref "D16") (pin "C") (pinfunction "C_C") (pintype "passive"))
      (node (ref "D17") (pin "C") (pinfunction "C_C") (pintype "passive"))
      (node (ref "D18") (pin "C") (pinfunction "C_C") (pintype "passive"))
      (node (ref "D19") (pin "C") (pinfunction "C_C") (pintype "passive"))
      (node (ref "U3") (pin "28") (pinfunction "PB15_28") (pintype "bidirectional"))
    )
    (net (code "109") (name "ROW2") (class "Default")
      (node (ref "D20") (pin "C") (pinfunction "C_C") (pintype "passive"))
      (node (ref "D21") (pin "C") (pinfunction "C_C") (pintype "passive"))
      (node (ref "D22") (pin "C") (pinfunction "C_C") (pintype "passive"))
      (node (ref "D23") (pin "C") (pinfunction "C_C") (pintype "passive"))
      (node (ref "D24") (pin "C") (pinfunction "C_C") (pintype "passive"))
      (node (ref "D25") (pin "C") (pinfunction "C_C") (pintype "passive"))
      (node (ref "D26") (pin "C") (pinfunction "C_C") (pintype "passive"))
      (node (ref "U3") (pin "27") (pinfunction "PB14_27") (pintype "bidirectional"))
    )
    (net (code "110") (name "ROW3") (class "Default")
      (node (ref "D27") (pin "C") (pinfunction "C_C") (pintype "passive"))
      (node (ref "D28") (pin "C") (pinfunction "C_C") (pintype "passive"))
      (node (ref "D29") (pin "C") (pinfunction "C_C") (pintype "passive"))
      (node (ref "D30") (pin "C") (pinfunction "C_C") (pintype "passive"))
      (node (ref "D31") (pin "C") (pinfunction "C_C") (pintype "passive"))
      (node (ref "D32") (pin "C") (pinfunction "C_C") (pintype "passive"))
      (node (ref "D33") (pin "C") (pinfunction "C_C") (pintype "passive"))
      (node (ref "U3") (pin "26") (pinfunction "PB13_26") (pintype "bidirectional"))
    )
    (net (code "111") (name "ROW4") (class "Default")
      (node (ref "D34") (pin "C") (pinfunction "C_C") (pintype "passive"))
      (node (ref "D35") (pin "C") (pinfunction "C_C") (pintype "passive"))
      (node (ref "D36") (pin "C") (pinfunction "C_C") (pintype "passive"))
      (node (ref "D37") (pin "C") (pinfunction "C_C") (pintype "passive"))
      (node (ref "D38") (pin "C") (pinfunction "C_C") (pintype "passive"))
      (node (ref "D39") (pin "C") (pinfunction "C_C") (pintype "passive"))
      (node (ref "U3") (pin "20") (pinfunction "PB2_20") (pintype "bidirectional"))
    )
    (net (code "112") (name "ROW5") (class "Default")
      (node (ref "D40") (pin "C") (pinfunction "C_C") (pintype "passive"))
      (node (ref "D41") (pin "C") (pinfunction "C_C") (pintype "passive"))
      (node (ref "D42") (pin "C") (pinfunction "C_C") (pintype "passive"))
      (node (ref "D43") (pin "C") (pinfunction "C_C") (pintype "passive"))
      (node (ref "D44") (pin "C") (pinfunction "C_C") (pintype "passive"))
      (node (ref "U3") (pin "13") (pinfunction "PA3_13") (pintype "bidirectional"))
    )
    (net (code "113") (name "SCL") (class "Default")
      (node (ref "J1") (pin "SCL") (pinfunction "2_SCL") (pintype "passive"))
      (node (ref "R7") (pin "1") (pinfunction "1_1") (pintype "passive"))
      (node (ref "U3") (pin "30") (pinfunction "I2C2_SCL/PA9_30") (pintype "bidirectional"))
      (node (ref "U4") (pin "6") (pinfunction "SCL_6") (pintype "bidirectional"))
      (node (ref "U5") (pin "5") (pinfunction "SCL_5") (pintype "bidirectional"))
    )
    (net (code "114") (name "SDA") (class "Default")
      (node (ref "J1") (pin "SDA") (pinfunction "1_SDA") (pintype "passive"))
      (node (ref "R8") (pin "1") (pinfunction "1_1") (pintype "passive"))
      (node (ref "U3") (pin "31") (pinfunction "I2C2_SDA/PA10_31") (pintype "bidirectional"))
      (node (ref "U4") (pin "5") (pinfunction "SDA_5") (pintype "bidirectional"))
      (node (ref "U5") (pin "6") (pinfunction "SDA_6") (pintype "bidirectional"))
    )
    (net (code "115") (name "SHIELD") (class "Default")
      (node (ref "C12") (pin "1") (pinfunction "1_1") (pintype "passive"))
      (node (ref "R4") (pin "1") (pinfunction "1_1") (pintype "passive"))
      (node (ref "X1") (pin "P$12") (pinfunction "SHEILD_P$12") (pintype "bidirectional"))
      (node (ref "X1") (pin "P$6") (pinfunction "SHEILD_P$6") (pintype "bidirectional"))
      (node (ref "X1") (pin "P$9") (pinfunction "SHEILD_P$9") (pintype "bidirectional"))
    )
    (net (code "116") (name "SWCLK") (class "Default")
      (node (ref "PH1") (pin "5") (pinfunction "5_5") (pintype "passive"))
      (node (ref "U3") (pin "37") (pinfunction "PA14/SWCLK-JTCK/I2C1_SDA_37") (pintype "bidirectional"))
    )
    (net (code "117") (name "SWDIO") (class "Default")
      (node (ref "PH1") (pin "4") (pinfunction "4_4") (pintype "passive"))
      (node (ref "U3") (pin "34") (pinfunction "PA13/SWDIO-JTMS_34") (pintype "bidirectional"))
    )
    (net (code "118") (name "VCC") (class "Default")
      (node (ref "C14") (pin "2") (pinfunction "2_2") (pintype "passive"))
      (node (ref "C7") (pin "2") (pinfunction "2_2") (pintype "passive"))
      (node (ref "D1") (pin "C") (pinfunction "C_C") (pintype "passive"))
      (node (ref "R10") (pin "1") (pinfunction "1_1") (pintype "passive"))
      (node (ref "R2") (pin "1") (pinfunction "1_1") (pintype "passive"))
      (node (ref "R6") (pin "2") (pinfunction "2_2") (pintype "passive"))
      (node (ref "SJ1") (pin "1") (pinfunction "1_1") (pintype "passive"))
      (node (ref "U1") (pin "3") (pinfunction "VI_3") (pintype "bidirectional"))
      (node (ref "U2") (pin "4") (pinfunction "4_4") (pintype "bidirectional"))
      (node (ref "U5") (pin "1") (pinfunction "VIN+_1") (pintype "bidirectional"))
      (node (ref "X1") (pin "VBUS1") (pinfunction "VBUS1_VBUS1") (pintype "input"))
      (node (ref "X1") (pin "VBUS2") (pinfunction "VBUS2_VBUS2") (pintype "passive"))
    )
    (net (code "119") (name "XTAL1") (class "Default")
      (node (ref "C10") (pin "2") (pinfunction "2_2") (pintype "passive"))
      (node (ref "U3") (pin "5") (pinfunction "PF0/OSC_IN/12C2_SDA_5") (pintype "bidirectional"))
      (node (ref "Y1") (pin "1") (pinfunction "1_1") (pintype "passive"))
    )
    (net (code "120") (name "XTAL2") (class "Default")
      (node (ref "C11") (pin "2") (pinfunction "2_2") (pintype "passive"))
      (node (ref "U3") (pin "6") (pinfunction "PF1/OSC_OUT/I2C2_SCL_6") (pintype "bidirectional"))
      (node (ref "Y1") (pin "3") (pinfunction "2_3") (pintype "passive"))
    )
    (net (code "121") (name "unconnected-(LED1-DO-PadDOUT)") (class "Default")
      (node (ref "LED1") (pin "DOUT") (pinfunction "DO_DOUT") (pintype "output"))
    )
    (net (code "122") (name "unconnected-(U3-I2C1_SCL{slash}JTDI{slash}PA15-Pad38)") (class "Default")
      (node (ref "U3") (pin "38") (pinfunction "I2C1_SCL/JTDI/PA15_38") (pintype "bidirectional"))
    )
    (net (code "123") (name "unconnected-(U3-I2C1_SCL{slash}PB6-Pad42)") (class "Default")
      (node (ref "U3") (pin "42") (pinfunction "I2C1_SCL/PB6_42") (pintype "bidirectional"))
    )
    (net (code "124") (name "unconnected-(U3-I2C1_SCL{slash}PB8-Pad45)") (class "Default")
      (node (ref "U3") (pin "45") (pinfunction "I2C1_SCL/PB8_45") (pintype "bidirectional"))
    )
    (net (code "125") (name "unconnected-(U3-I2C1_SDA{slash}PB7-Pad43)") (class "Default")
      (node (ref "U3") (pin "43") (pinfunction "I2C1_SDA/PB7_43") (pintype "bidirectional"))
    )
    (net (code "126") (name "unconnected-(U3-I2C1_SDA{slash}PB9-Pad46)") (class "Default")
      (node (ref "U3") (pin "46") (pinfunction "I2C1_SDA/PB9_46") (pintype "bidirectional"))
    )
    (net (code "127") (name "unconnected-(U3-JNTRST{slash}PB4-Pad40)") (class "Default")
      (node (ref "U3") (pin "40") (pinfunction "JNTRST/PB4_40") (pintype "bidirectional"))
    )
    (net (code "128") (name "unconnected-(U3-JTDO{slash}TRACEWO{slash}PB3-Pad39)") (class "Default")
      (node (ref "U3") (pin "39") (pinfunction "JTDO/TRACEWO/PB3_39") (pintype "bidirectional"))
    )
    (net (code "129") (name "unconnected-(U3-PA0-Pad10)") (class "Default")
      (node (ref "U3") (pin "10") (pinfunction "PA0_10") (pintype "bidirectional"))
    )
    (net (code "130") (name "unconnected-(U3-PB5-Pad41)") (class "Default")
      (node (ref "U3") (pin "41") (pinfunction "PB5_41") (pintype "bidirectional"))
    )
    (net (code "131") (name "unconnected-(U3-PC13-Pad2)") (class "Default")
      (node (ref "U3") (pin "2") (pinfunction "PC13_2") (pintype "bidirectional"))
    )
    (net (code "132") (name "unconnected-(U3-PC14{slash}OSC32_IN-Pad3)") (class "Default")
      (node (ref "U3") (pin "3") (pinfunction "PC14/OSC32_IN_3") (pintype "bidirectional"))
    )
    (net (code "133") (name "unconnected-(U3-PC15{slash}OSC32_OUT-Pad4)") (class "Default")
      (node (ref "U3") (pin "4") (pinfunction "PC15/OSC32_OUT_4") (pintype "bidirectional"))
    )
    (net (code "134") (name "unconnected-(U4-A0-Pad1)") (class "Default")
      (node (ref "U4") (pin "1") (pinfunction "A0_1") (pintype "bidirectional"))
    )
    (net (code "135") (name "unconnected-(U4-A1-Pad2)") (class "Default")
      (node (ref "U4") (pin "2") (pinfunction "A1_2") (pintype "bidirectional"))
    )
    (net (code "136") (name "unconnected-(U4-A2-Pad3)") (class "Default")
      (node (ref "U4") (pin "3") (pinfunction "A2_3") (pintype "bidirectional"))
    )
    (net (code "137") (name "unconnected-(U4-WP-Pad7)") (class "Default")
      (node (ref "U4") (pin "7") (pinfunction "WP_7") (pintype "bidirectional"))
    )
    (net (code "138") (name "unconnected-(U5-A0-Pad7)") (class "Default")
      (node (ref "U5") (pin "7") (pinfunction "A0_7") (pintype "bidirectional"))
    )
    (net (code "139") (name "unconnected-(U5-A1-Pad8)") (class "Default")
      (node (ref "U5") (pin "8") (pinfunction "A1_8") (pintype "bidirectional"))
    )
    (net (code "140") (name "unconnected-(X1-PadSBU1)") (class "Default")
      (node (ref "X1") (pin "SBU1") (pinfunction "SBU1_SBU1") (pintype "passive"))
    )
    (net (code "141") (name "unconnected-(X1-PadSBU2)") (class "Default")
      (node (ref "X1") (pin "SBU2") (pinfunction "SBU2_SBU2") (pintype "input"))
    )
  )
)
